# RAMBo.net
KiCad netlist of a schematic drawn in EAGLE
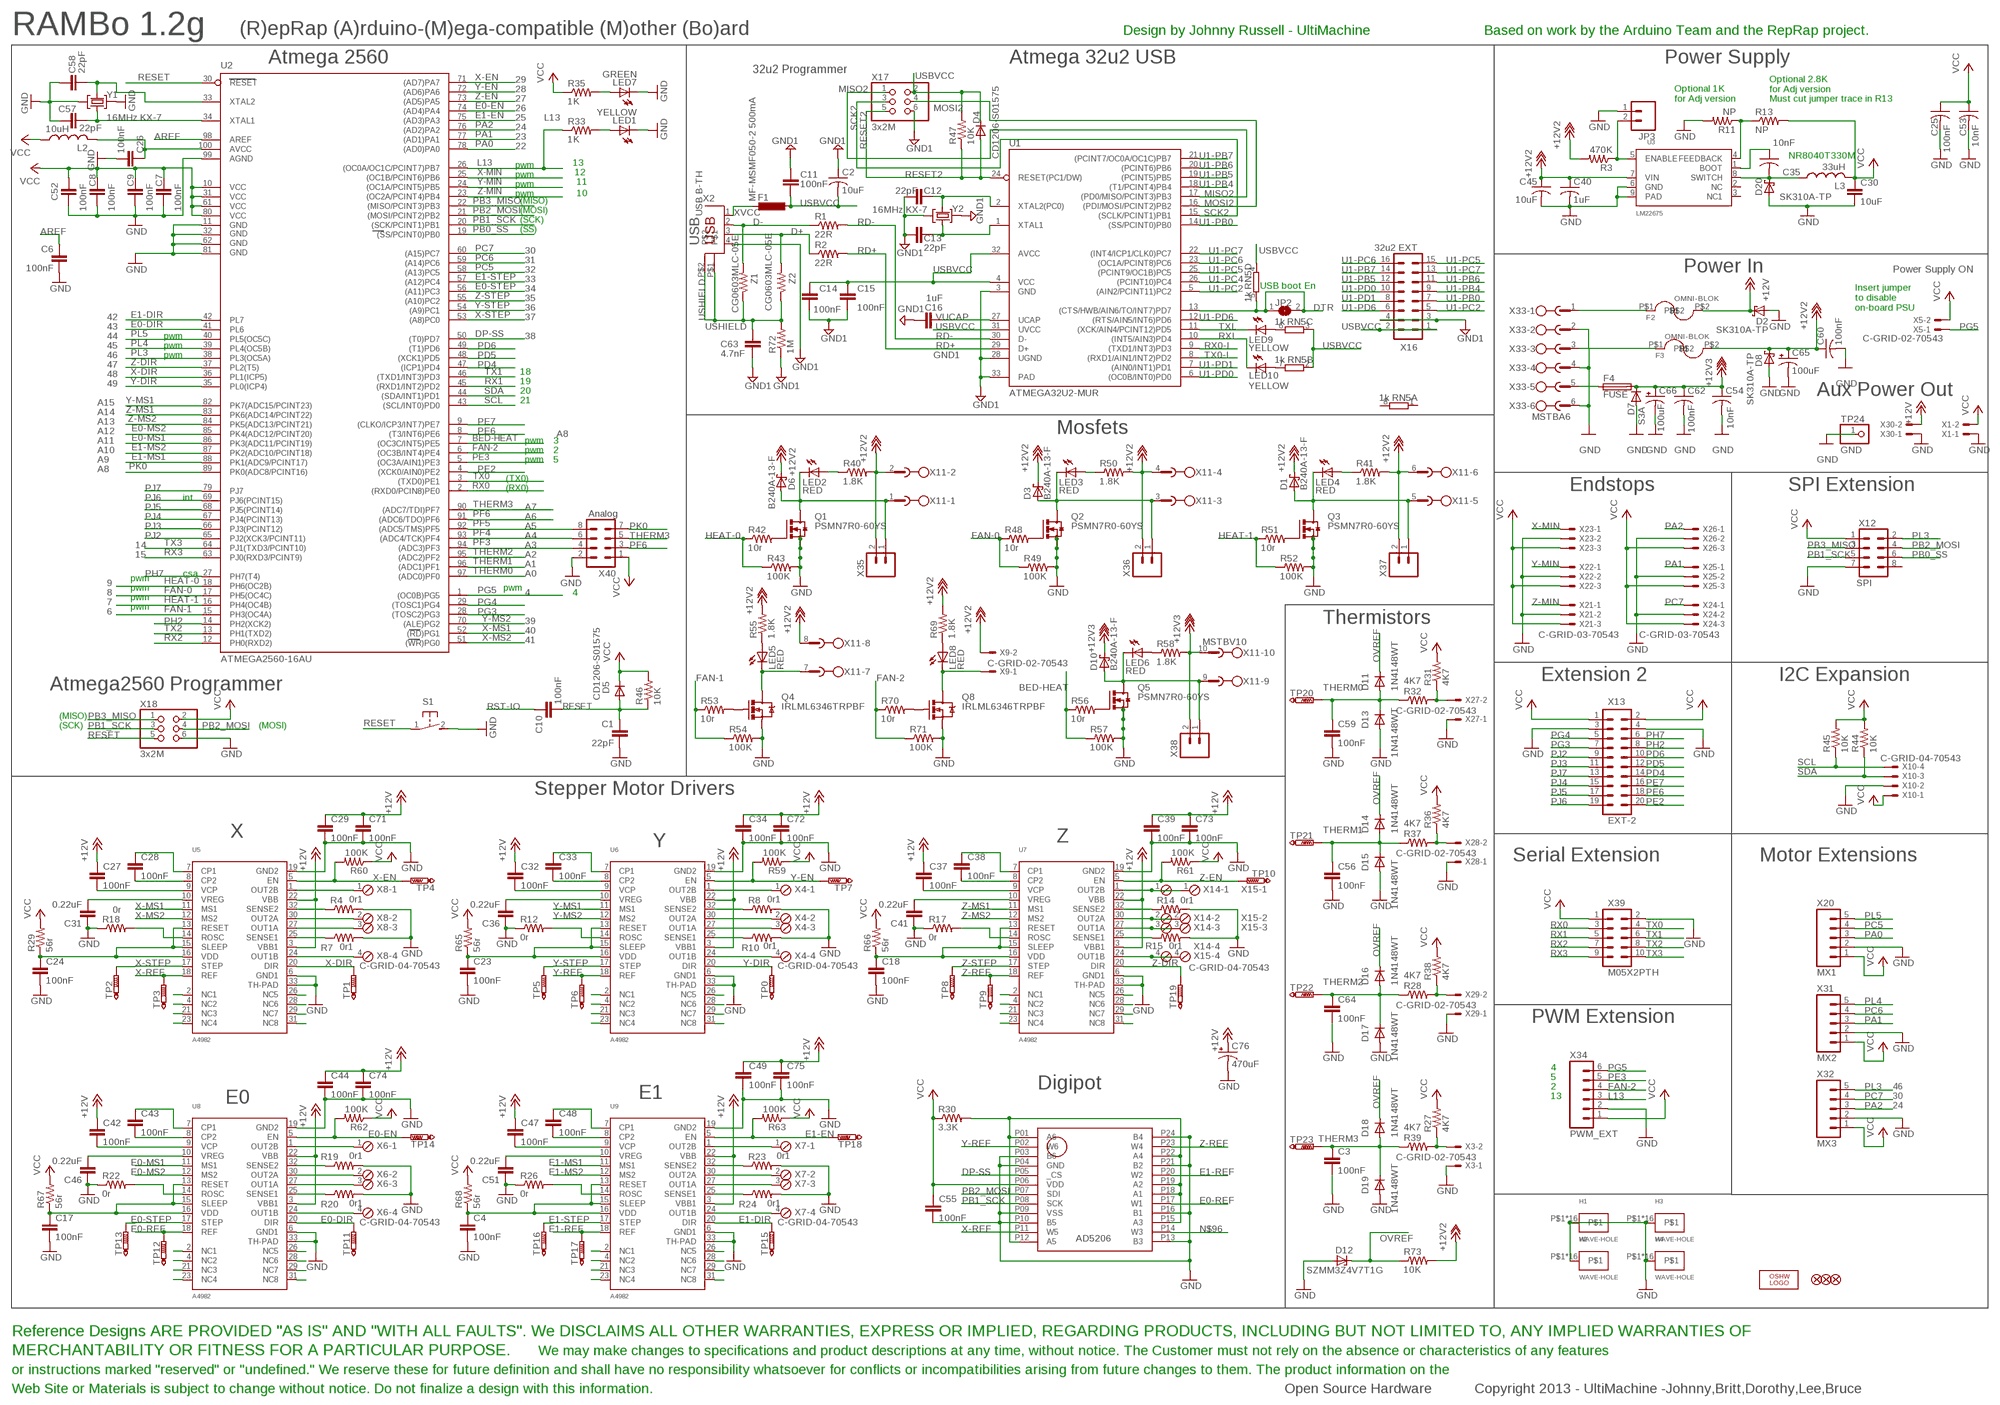
[diagram p0: schematic, sheet 1, part 1 of 2]
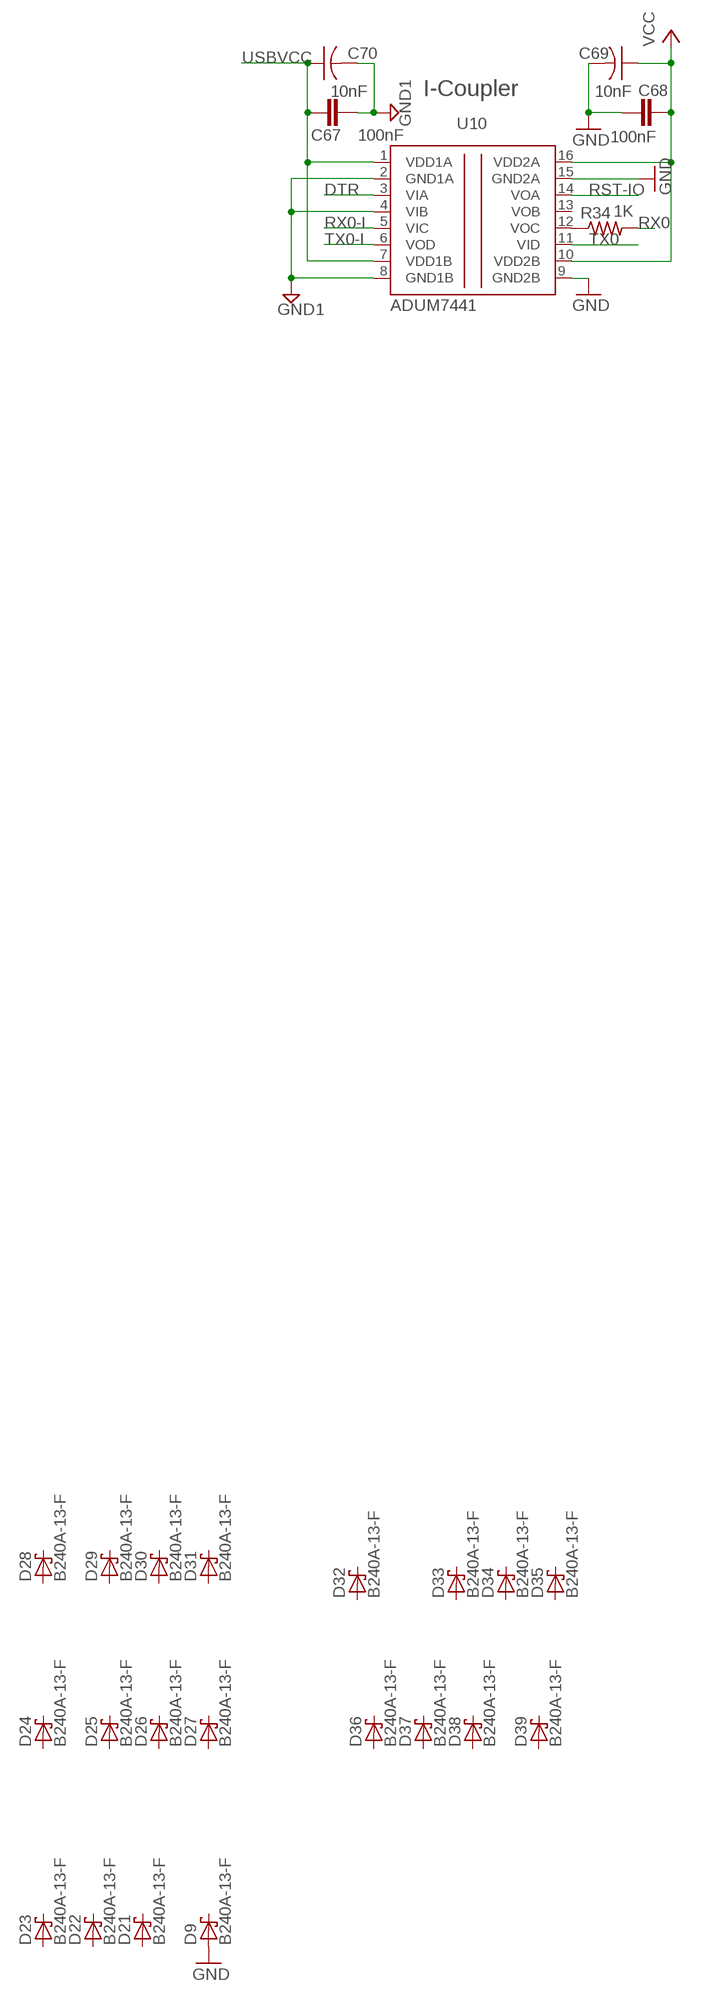
[diagram p1: schematic, sheet 1, part 2 of 2]

(export (version "E")
  (design (tool "Eeschema 10.0.6"))
  (components
    (comp (ref "C1")
      (value "22pF")
      (footprint "eagle-import:C0603")
      (libsource (lib "eagle-import") (part "resistor_C-EUC0603"))
    )
    (comp (ref "C2")
      (value "10uF")
      (footprint "eagle-import:C0805")
      (libsource (lib "eagle-import") (part "C-USC0805"))
    )
    (comp (ref "C3")
      (value "100nF")
      (footprint "eagle-import:C0603")
      (libsource (lib "eagle-import") (part "resistor_C-EUC0603"))
    )
    (comp (ref "C4")
      (value "100nF")
      (footprint "eagle-import:C0603")
      (libsource (lib "eagle-import") (part "resistor_C-EUC0603"))
    )
    (comp (ref "C6")
      (value "100nF")
      (footprint "eagle-import:C0603")
      (libsource (lib "eagle-import") (part "resistor_C-EUC0603"))
    )
    (comp (ref "C7")
      (value "100nF")
      (footprint "eagle-import:C0603")
      (libsource (lib "eagle-import") (part "resistor_C-EUC0603"))
    )
    (comp (ref "C8")
      (value "100nF")
      (footprint "eagle-import:C0603")
      (libsource (lib "eagle-import") (part "resistor_C-EUC0603"))
    )
    (comp (ref "C9")
      (value "100nF")
      (footprint "eagle-import:C0603")
      (libsource (lib "eagle-import") (part "resistor_C-EUC0603"))
    )
    (comp (ref "C10")
      (value "100nF")
      (footprint "eagle-import:C0603")
      (libsource (lib "eagle-import") (part "resistor_C-EUC0603"))
    )
    (comp (ref "C11")
      (value "100nF")
      (footprint "eagle-import:C0603")
      (libsource (lib "eagle-import") (part "resistor_C-EUC0603"))
    )
    (comp (ref "C12")
      (value "22pF")
      (footprint "eagle-import:C0603")
      (libsource (lib "eagle-import") (part "resistor_C-EUC0603"))
    )
    (comp (ref "C13")
      (value "22pF")
      (footprint "eagle-import:C0603")
      (libsource (lib "eagle-import") (part "resistor_C-EUC0603"))
    )
    (comp (ref "C14")
      (value "100nF")
      (footprint "eagle-import:C0603")
      (libsource (lib "eagle-import") (part "resistor_C-EUC0603"))
    )
    (comp (ref "C15")
      (value "100nF")
      (footprint "eagle-import:C0603")
      (libsource (lib "eagle-import") (part "resistor_C-EUC0603"))
    )
    (comp (ref "C16")
      (value "1uF")
      (footprint "eagle-import:C0603")
      (libsource (lib "eagle-import") (part "resistor_C-EUC0603"))
    )
    (comp (ref "C17")
      (value "100nF")
      (footprint "eagle-import:C0603")
      (libsource (lib "eagle-import") (part "resistor_C-EUC0603"))
    )
    (comp (ref "C18")
      (value "100nF")
      (footprint "eagle-import:C0603")
      (libsource (lib "eagle-import") (part "resistor_C-EUC0603"))
    )
    (comp (ref "C23")
      (value "100nF")
      (footprint "eagle-import:C0603")
      (libsource (lib "eagle-import") (part "resistor_C-EUC0603"))
    )
    (comp (ref "C24")
      (value "100nF")
      (footprint "eagle-import:C0603")
      (libsource (lib "eagle-import") (part "resistor_C-EUC0603"))
    )
    (comp (ref "C25")
      (value "100nF")
      (footprint "eagle-import:C0603")
      (libsource (lib "eagle-import") (part "C-USC0603"))
    )
    (comp (ref "C26")
      (value "100nF")
      (footprint "eagle-import:C0603")
      (libsource (lib "eagle-import") (part "resistor_C-EUC0603"))
    )
    (comp (ref "C27")
      (value "100nF")
      (footprint "eagle-import:C0603")
      (libsource (lib "eagle-import") (part "resistor_C-EUC0603"))
    )
    (comp (ref "C28")
      (value "100nF")
      (footprint "eagle-import:C0603")
      (libsource (lib "eagle-import") (part "resistor_C-EUC0603"))
    )
    (comp (ref "C29")
      (value "100nF")
      (footprint "eagle-import:C0603")
      (libsource (lib "eagle-import") (part "resistor_C-EUC0603"))
    )
    (comp (ref "C30")
      (value "10uF")
      (footprint "eagle-import:C1210K")
      (libsource (lib "eagle-import") (part "resistor_C-EUC1210K"))
    )
    (comp (ref "C31")
      (value "0.22uF")
      (footprint "eagle-import:C0603")
      (libsource (lib "eagle-import") (part "resistor_C-EUC0603"))
    )
    (comp (ref "C32")
      (value "100nF")
      (footprint "eagle-import:C0603")
      (libsource (lib "eagle-import") (part "resistor_C-EUC0603"))
    )
    (comp (ref "C33")
      (value "100nF")
      (footprint "eagle-import:C0603")
      (libsource (lib "eagle-import") (part "resistor_C-EUC0603"))
    )
    (comp (ref "C34")
      (value "100nF")
      (footprint "eagle-import:C0603")
      (libsource (lib "eagle-import") (part "resistor_C-EUC0603"))
    )
    (comp (ref "C35")
      (value "10nF")
      (footprint "eagle-import:C0603")
      (libsource (lib "eagle-import") (part "C-USC0603"))
    )
    (comp (ref "C36")
      (value "0.22uF")
      (footprint "eagle-import:C0603")
      (libsource (lib "eagle-import") (part "resistor_C-EUC0603"))
    )
    (comp (ref "C37")
      (value "100nF")
      (footprint "eagle-import:C0603")
      (libsource (lib "eagle-import") (part "resistor_C-EUC0603"))
    )
    (comp (ref "C38")
      (value "100nF")
      (footprint "eagle-import:C0603")
      (libsource (lib "eagle-import") (part "resistor_C-EUC0603"))
    )
    (comp (ref "C39")
      (value "100nF")
      (footprint "eagle-import:C0603")
      (libsource (lib "eagle-import") (part "resistor_C-EUC0603"))
    )
    (comp (ref "C40")
      (value "1uF")
      (footprint "eagle-import:C0805")
      (libsource (lib "eagle-import") (part "C-USC0805"))
    )
    (comp (ref "C41")
      (value "0.22uF")
      (footprint "eagle-import:C0603")
      (libsource (lib "eagle-import") (part "resistor_C-EUC0603"))
    )
    (comp (ref "C42")
      (value "100nF")
      (footprint "eagle-import:C0603")
      (libsource (lib "eagle-import") (part "resistor_C-EUC0603"))
    )
    (comp (ref "C43")
      (value "100nF")
      (footprint "eagle-import:C0603")
      (libsource (lib "eagle-import") (part "resistor_C-EUC0603"))
    )
    (comp (ref "C44")
      (value "100nF")
      (footprint "eagle-import:C0603")
      (libsource (lib "eagle-import") (part "resistor_C-EUC0603"))
    )
    (comp (ref "C45")
      (value "10uF")
      (footprint "eagle-import:C2220K")
      (libsource (lib "eagle-import") (part "C-USC2220K"))
    )
    (comp (ref "C46")
      (value "0.22uF")
      (footprint "eagle-import:C0603")
      (libsource (lib "eagle-import") (part "resistor_C-EUC0603"))
    )
    (comp (ref "C47")
      (value "100nF")
      (footprint "eagle-import:C0603")
      (libsource (lib "eagle-import") (part "resistor_C-EUC0603"))
    )
    (comp (ref "C48")
      (value "100nF")
      (footprint "eagle-import:C0603")
      (libsource (lib "eagle-import") (part "resistor_C-EUC0603"))
    )
    (comp (ref "C49")
      (value "100nF")
      (footprint "eagle-import:C0603")
      (libsource (lib "eagle-import") (part "resistor_C-EUC0603"))
    )
    (comp (ref "C51")
      (value "0.22uF")
      (footprint "eagle-import:C0603")
      (libsource (lib "eagle-import") (part "resistor_C-EUC0603"))
    )
    (comp (ref "C52")
      (value "100nF")
      (footprint "eagle-import:C0603")
      (libsource (lib "eagle-import") (part "resistor_C-EUC0603"))
    )
    (comp (ref "C53")
      (value "10nF")
      (footprint "eagle-import:C0603")
      (libsource (lib "eagle-import") (part "C-USC0603"))
    )
    (comp (ref "C54")
      (value "10nF")
      (footprint "eagle-import:C0603")
      (libsource (lib "eagle-import") (part "C-USC0603"))
    )
    (comp (ref "C55")
      (value "100nF")
      (footprint "eagle-import:C0603")
      (libsource (lib "eagle-import") (part "resistor_C-EUC0603"))
    )
    (comp (ref "C56")
      (value "100nF")
      (footprint "eagle-import:C0603")
      (libsource (lib "eagle-import") (part "resistor_C-EUC0603"))
    )
    (comp (ref "C57")
      (value "22pF")
      (footprint "eagle-import:C0603")
      (libsource (lib "eagle-import") (part "resistor_C-EUC0603"))
    )
    (comp (ref "C58")
      (value "22pF")
      (footprint "eagle-import:C0603")
      (libsource (lib "eagle-import") (part "resistor_C-EUC0603"))
    )
    (comp (ref "C59")
      (value "100nF")
      (footprint "eagle-import:C0603")
      (libsource (lib "eagle-import") (part "resistor_C-EUC0603"))
    )
    (comp (ref "C60")
      (value "100nF")
      (footprint "eagle-import:C0603")
      (libsource (lib "eagle-import") (part "C-USC0603"))
    )
    (comp (ref "C62")
      (value "100nF")
      (footprint "eagle-import:C0603")
      (libsource (lib "eagle-import") (part "C-USC0603"))
    )
    (comp (ref "C63")
      (value "4.7nF")
      (footprint "eagle-import:C0402")
      (libsource (lib "eagle-import") (part "C-EUC0402"))
    )
    (comp (ref "C64")
      (value "100nF")
      (footprint "eagle-import:C0603")
      (libsource (lib "eagle-import") (part "resistor_C-EUC0603"))
    )
    (comp (ref "C65")
      (value "100uF")
      (footprint "eagle-import:E3,5-8")
      (libsource (lib "eagle-import") (part "CPOL-USE3.5-8"))
    )
    (comp (ref "C66")
      (value "100uF")
      (footprint "eagle-import:E3,5-8")
      (libsource (lib "eagle-import") (part "CPOL-USE3.5-8"))
    )
    (comp (ref "C67")
      (value "100nF")
      (footprint "eagle-import:C0603")
      (libsource (lib "eagle-import") (part "resistor_C-EUC0603"))
    )
    (comp (ref "C68")
      (value "100nF")
      (footprint "eagle-import:C0603")
      (libsource (lib "eagle-import") (part "resistor_C-EUC0603"))
    )
    (comp (ref "C69")
      (value "10nF")
      (footprint "eagle-import:C0603")
      (libsource (lib "eagle-import") (part "C-USC0603"))
    )
    (comp (ref "C70")
      (value "10nF")
      (footprint "eagle-import:C0603")
      (libsource (lib "eagle-import") (part "C-USC0603"))
    )
    (comp (ref "C71")
      (value "100nF")
      (footprint "eagle-import:C0603")
      (libsource (lib "eagle-import") (part "resistor_C-EUC0603"))
    )
    (comp (ref "C72")
      (value "100nF")
      (footprint "eagle-import:C0603")
      (libsource (lib "eagle-import") (part "resistor_C-EUC0603"))
    )
    (comp (ref "C73")
      (value "100nF")
      (footprint "eagle-import:C0603")
      (libsource (lib "eagle-import") (part "resistor_C-EUC0603"))
    )
    (comp (ref "C74")
      (value "100nF")
      (footprint "eagle-import:C0603")
      (libsource (lib "eagle-import") (part "resistor_C-EUC0603"))
    )
    (comp (ref "C75")
      (value "100nF")
      (footprint "eagle-import:C0603")
      (libsource (lib "eagle-import") (part "resistor_C-EUC0603"))
    )
    (comp (ref "C76")
      (value "470uF")
      (footprint "eagle-import:C12,5-5")
      (libsource (lib "eagle-import") (part "CPOL-USC12,5-5"))
    )
    (comp (ref "D1")
      (value "B240A-13-F")
      (footprint "eagle-import:SMA-SM")
      (libsource (lib "eagle-import") (part "SCHOTTKY-DIODE"))
    )
    (comp (ref "D2")
      (value "SK310A-TP")
      (footprint "eagle-import:SMA-SM")
      (libsource (lib "eagle-import") (part "SCHOTTKY-DIODE"))
    )
    (comp (ref "D3")
      (value "B240A-13-F")
      (footprint "eagle-import:SMA-SM")
      (libsource (lib "eagle-import") (part "SCHOTTKY-DIODE"))
    )
    (comp (ref "D4")
      (value "CD1206-S01575")
      (footprint "eagle-import:MINIMELF")
      (libsource (lib "eagle-import") (part "DIODE-MINIMELF"))
    )
    (comp (ref "D5")
      (value "CD1206-S01575")
      (footprint "eagle-import:MINIMELF")
      (libsource (lib "eagle-import") (part "DIODE-MINIMELF"))
    )
    (comp (ref "D6")
      (value "B240A-13-F")
      (footprint "eagle-import:SMA-SM")
      (libsource (lib "eagle-import") (part "SCHOTTKY-DIODE"))
    )
    (comp (ref "D7")
      (value "S3A")
      (footprint "eagle-import:DO-214AB")
      (libsource (lib "eagle-import") (part "DIODE-D0-214AB"))
    )
    (comp (ref "D8")
      (value "SK310A-TP")
      (footprint "eagle-import:SMA-SM")
      (libsource (lib "eagle-import") (part "SCHOTTKY-DIODE"))
    )
    (comp (ref "D9")
      (value "B240A-13-F")
      (footprint "eagle-import:SMA-SM")
      (libsource (lib "eagle-import") (part "SCHOTTKY-DIODE"))
    )
    (comp (ref "D10")
      (value "B240A-13-F")
      (footprint "eagle-import:SMA-SM")
      (libsource (lib "eagle-import") (part "SCHOTTKY-DIODE"))
    )
    (comp (ref "D11")
      (value "1N4148WT")
      (footprint "eagle-import:SOD523")
      (libsource (lib "eagle-import") (part "1N4148WT"))
    )
    (comp (ref "D12")
      (value "SZMM3Z4V7T1G")
      (footprint "eagle-import:SOD323-R")
      (libsource (lib "eagle-import") (part "ZENER-DIODESOD323"))
    )
    (comp (ref "D13")
      (value "1N4148WT")
      (footprint "eagle-import:SOD523")
      (libsource (lib "eagle-import") (part "1N4148WT"))
    )
    (comp (ref "D14")
      (value "1N4148WT")
      (footprint "eagle-import:SOD523")
      (libsource (lib "eagle-import") (part "1N4148WT"))
    )
    (comp (ref "D15")
      (value "1N4148WT")
      (footprint "eagle-import:SOD523")
      (libsource (lib "eagle-import") (part "1N4148WT"))
    )
    (comp (ref "D16")
      (value "1N4148WT")
      (footprint "eagle-import:SOD523")
      (libsource (lib "eagle-import") (part "1N4148WT"))
    )
    (comp (ref "D17")
      (value "1N4148WT")
      (footprint "eagle-import:SOD523")
      (libsource (lib "eagle-import") (part "1N4148WT"))
    )
    (comp (ref "D18")
      (value "1N4148WT")
      (footprint "eagle-import:SOD523")
      (libsource (lib "eagle-import") (part "1N4148WT"))
    )
    (comp (ref "D19")
      (value "1N4148WT")
      (footprint "eagle-import:SOD523")
      (libsource (lib "eagle-import") (part "1N4148WT"))
    )
    (comp (ref "D20")
      (value "SK310A-TP")
      (footprint "eagle-import:SMA-SM")
      (libsource (lib "eagle-import") (part "SCHOTTKY-DIODE"))
    )
    (comp (ref "D21")
      (value "B240A-13-F")
      (footprint "eagle-import:SMA-SM")
      (libsource (lib "eagle-import") (part "SCHOTTKY-DIODE"))
    )
    (comp (ref "D22")
      (value "B240A-13-F")
      (footprint "eagle-import:SMA-SM")
      (libsource (lib "eagle-import") (part "SCHOTTKY-DIODE"))
    )
    (comp (ref "D23")
      (value "B240A-13-F")
      (footprint "eagle-import:SMA-SM")
      (libsource (lib "eagle-import") (part "SCHOTTKY-DIODE"))
    )
    (comp (ref "D24")
      (value "B240A-13-F")
      (footprint "eagle-import:SMA-SM")
      (libsource (lib "eagle-import") (part "SCHOTTKY-DIODE"))
    )
    (comp (ref "D25")
      (value "B240A-13-F")
      (footprint "eagle-import:SMA-SM")
      (libsource (lib "eagle-import") (part "SCHOTTKY-DIODE"))
    )
    (comp (ref "D26")
      (value "B240A-13-F")
      (footprint "eagle-import:SMA-SM")
      (libsource (lib "eagle-import") (part "SCHOTTKY-DIODE"))
    )
    (comp (ref "D27")
      (value "B240A-13-F")
      (footprint "eagle-import:SMA-SM")
      (libsource (lib "eagle-import") (part "SCHOTTKY-DIODE"))
    )
    (comp (ref "D28")
      (value "B240A-13-F")
      (footprint "eagle-import:SMA-SM")
      (libsource (lib "eagle-import") (part "SCHOTTKY-DIODE"))
    )
    (comp (ref "D29")
      (value "B240A-13-F")
      (footprint "eagle-import:SMA-SM")
      (libsource (lib "eagle-import") (part "SCHOTTKY-DIODE"))
    )
    (comp (ref "D30")
      (value "B240A-13-F")
      (footprint "eagle-import:SMA-SM")
      (libsource (lib "eagle-import") (part "SCHOTTKY-DIODE"))
    )
    (comp (ref "D31")
      (value "B240A-13-F")
      (footprint "eagle-import:SMA-SM")
      (libsource (lib "eagle-import") (part "SCHOTTKY-DIODE"))
    )
    (comp (ref "D32")
      (value "B240A-13-F")
      (footprint "eagle-import:SMA-SM")
      (libsource (lib "eagle-import") (part "SCHOTTKY-DIODE"))
    )
    (comp (ref "D33")
      (value "B240A-13-F")
      (footprint "eagle-import:SMA-SM")
      (libsource (lib "eagle-import") (part "SCHOTTKY-DIODE"))
    )
    (comp (ref "D34")
      (value "B240A-13-F")
      (footprint "eagle-import:SMA-SM")
      (libsource (lib "eagle-import") (part "SCHOTTKY-DIODE"))
    )
    (comp (ref "D35")
      (value "B240A-13-F")
      (footprint "eagle-import:SMA-SM")
      (libsource (lib "eagle-import") (part "SCHOTTKY-DIODE"))
    )
    (comp (ref "D36")
      (value "B240A-13-F")
      (footprint "eagle-import:SMA-SM")
      (libsource (lib "eagle-import") (part "SCHOTTKY-DIODE"))
    )
    (comp (ref "D37")
      (value "B240A-13-F")
      (footprint "eagle-import:SMA-SM")
      (libsource (lib "eagle-import") (part "SCHOTTKY-DIODE"))
    )
    (comp (ref "D38")
      (value "B240A-13-F")
      (footprint "eagle-import:SMA-SM")
      (libsource (lib "eagle-import") (part "SCHOTTKY-DIODE"))
    )
    (comp (ref "D39")
      (value "B240A-13-F")
      (footprint "eagle-import:SMA-SM")
      (libsource (lib "eagle-import") (part "SCHOTTKY-DIODE"))
    )
    (comp (ref "F1")
      (value "MF-MSMF050-2 500mA")
      (footprint "eagle-import:L1812")
      (libsource (lib "eagle-import") (part "L-EUL1812"))
    )
    (comp (ref "F2")
      (value "OMNI-BLOK")
      (footprint "eagle-import:OMNI-BLOK")
      (libsource (lib "eagle-import") (part "OMNI-BLOK"))
    )
    (comp (ref "F3")
      (value "OMNI-BLOK")
      (footprint "eagle-import:OMNI-BLOK")
      (libsource (lib "eagle-import") (part "OMNI-BLOK"))
    )
    (comp (ref "F4")
      (value "FUSE")
      (footprint "eagle-import:FUSE-ATO-SMD")
      (libsource (lib "eagle-import") (part "FUSE"))
    )
    (comp (ref "FID1")
      (value "FIDUCIAL1X2")
      (footprint "eagle-import:FIDUCIAL-1X2")
      (libsource (lib "eagle-import") (part "FIDUCIAL1X2"))
    )
    (comp (ref "FID2")
      (value "FIDUCIAL1X2")
      (footprint "eagle-import:FIDUCIAL-1X2")
      (libsource (lib "eagle-import") (part "FIDUCIAL1X2"))
    )
    (comp (ref "FID3")
      (value "FIDUCIAL1X2")
      (footprint "eagle-import:FIDUCIAL-1X2")
      (libsource (lib "eagle-import") (part "FIDUCIAL1X2"))
    )
    (comp (ref "H1")
      (value "WAVE-HOLE")
      (footprint "eagle-import:3,0-WAVE-HOLE")
      (libsource (lib "eagle-import") (part "WAVE-HOLE"))
    )
    (comp (ref "H2")
      (value "WAVE-HOLE")
      (footprint "eagle-import:3,0-WAVE-HOLE")
      (libsource (lib "eagle-import") (part "WAVE-HOLE"))
    )
    (comp (ref "H3")
      (value "WAVE-HOLE")
      (footprint "eagle-import:3,0-WAVE-HOLE")
      (libsource (lib "eagle-import") (part "WAVE-HOLE"))
    )
    (comp (ref "H4")
      (value "WAVE-HOLE")
      (footprint "eagle-import:3,0-WAVE-HOLE")
      (libsource (lib "eagle-import") (part "WAVE-HOLE"))
    )
    (comp (ref "JP2") (value "SJ") (footprint "eagle-import:SJ") (libsource (lib "eagle-import") (part "SJ")))
    (comp (ref "JP3")
      (value "M02PTH")
      (footprint "eagle-import:1X02")
      (libsource (lib "eagle-import") (part "M02PTH"))
    )
    (comp (ref "L2")
      (value "10uH")
      (footprint "eagle-import:C0805")
      (libsource (lib "eagle-import") (part "L-US"))
    )
    (comp (ref "L3")
      (value "33uH")
      (footprint "eagle-import:NR8040")
      (libsource (lib "eagle-import") (part "L-USNR8040"))
    )
    (comp (ref "LED1")
      (value "YELLOW")
      (footprint "eagle-import:CHIP-LED0805")
      (libsource (lib "eagle-import") (part "LEDCHIP-LED0805"))
    )
    (comp (ref "LED2")
      (value "RED")
      (footprint "eagle-import:CHIP-LED0805")
      (libsource (lib "eagle-import") (part "LEDCHIP-LED0805"))
    )
    (comp (ref "LED3")
      (value "RED")
      (footprint "eagle-import:CHIP-LED0805")
      (libsource (lib "eagle-import") (part "LEDCHIP-LED0805"))
    )
    (comp (ref "LED4")
      (value "RED")
      (footprint "eagle-import:CHIP-LED0805")
      (libsource (lib "eagle-import") (part "LEDCHIP-LED0805"))
    )
    (comp (ref "LED5")
      (value "RED")
      (footprint "eagle-import:CHIP-LED0805")
      (libsource (lib "eagle-import") (part "LEDCHIP-LED0805"))
    )
    (comp (ref "LED6")
      (value "RED")
      (footprint "eagle-import:CHIP-LED0805")
      (libsource (lib "eagle-import") (part "LEDCHIP-LED0805"))
    )
    (comp (ref "LED7")
      (value "GREEN")
      (footprint "eagle-import:CHIP-LED0805")
      (libsource (lib "eagle-import") (part "LEDCHIP-LED0805"))
    )
    (comp (ref "LED8")
      (value "RED")
      (footprint "eagle-import:CHIP-LED0805")
      (libsource (lib "eagle-import") (part "LEDCHIP-LED0805"))
    )
    (comp (ref "LED9")
      (value "YELLOW")
      (footprint "eagle-import:CHIP-LED0805")
      (libsource (lib "eagle-import") (part "LEDCHIP-LED0805"))
    )
    (comp (ref "LED10")
      (value "YELLOW")
      (footprint "eagle-import:CHIP-LED0805")
      (libsource (lib "eagle-import") (part "LEDCHIP-LED0805"))
    )
    (comp (ref "LOGO1")
      (value "OSHW_LOGO_8MILX0150-NT")
      (footprint "eagle-import:OSHW_8X150_NOTEXT")
      (libsource (lib "eagle-import") (part "OSHW_LOGO_8MILX0150-NT"))
    )
    (comp (ref "Q1")
      (value "PSMN7R0-60YS")
      (footprint "eagle-import:SOT669")
      (libsource (lib "eagle-import") (part "PH7030L"))
    )
    (comp (ref "Q2")
      (value "PSMN7R0-60YS")
      (footprint "eagle-import:SOT669")
      (libsource (lib "eagle-import") (part "PH7030L"))
    )
    (comp (ref "Q3")
      (value "PSMN7R0-60YS")
      (footprint "eagle-import:SOT669")
      (libsource (lib "eagle-import") (part "PH7030L"))
    )
    (comp (ref "Q4")
      (value "IRLML6346TRPBF")
      (footprint "eagle-import:SOT23-3")
      (libsource (lib "eagle-import") (part "MOSFET-NCHANNELSMD"))
    )
    (comp (ref "Q5")
      (value "PSMN7R0-60YS")
      (footprint "eagle-import:SOT669")
      (libsource (lib "eagle-import") (part "PH7030L"))
    )
    (comp (ref "Q8")
      (value "IRLML6346TRPBF")
      (footprint "eagle-import:SOT23-3")
      (libsource (lib "eagle-import") (part "MOSFET-NCHANNELSMD"))
    )
    (comp (ref "R1")
      (value "22R")
      (footprint "eagle-import:R0402")
      (libsource (lib "eagle-import") (part "R-US_R0402"))
    )
    (comp (ref "R2")
      (value "22R")
      (footprint "eagle-import:R0402")
      (libsource (lib "eagle-import") (part "R-US_R0402"))
    )
    (comp (ref "R3")
      (value "470K")
      (footprint "eagle-import:R0603")
      (libsource (lib "eagle-import") (part "resistor_R-US_R0603"))
    )
    (comp (ref "R4")
      (value "0r1")
      (footprint "eagle-import:R1206")
      (libsource (lib "eagle-import") (part "resistor_R-US_R1206"))
    )
    (comp (ref "R7")
      (value "0r1")
      (footprint "eagle-import:R1206")
      (libsource (lib "eagle-import") (part "resistor_R-US_R1206"))
    )
    (comp (ref "R8")
      (value "0r1")
      (footprint "eagle-import:R1206")
      (libsource (lib "eagle-import") (part "resistor_R-US_R1206"))
    )
    (comp (ref "R10")
      (value "0r1")
      (footprint "eagle-import:R1206")
      (libsource (lib "eagle-import") (part "resistor_R-US_R1206"))
    )
    (comp (ref "R11")
      (value "NP")
      (footprint "eagle-import:R0603")
      (libsource (lib "eagle-import") (part "resistor_R-US_R0603"))
    )
    (comp (ref "R12")
      (value "0r")
      (footprint "eagle-import:R0603")
      (libsource (lib "eagle-import") (part "resistor_R-US_R0603"))
    )
    (comp (ref "R13")
      (value "NP")
      (footprint "eagle-import:R0603")
      (libsource (lib "eagle-import") (part "resistor_R-US_R0603"))
    )
    (comp (ref "R14")
      (value "0r1")
      (footprint "eagle-import:R1206")
      (libsource (lib "eagle-import") (part "resistor_R-US_R1206"))
    )
    (comp (ref "R15")
      (value "0r1")
      (footprint "eagle-import:R1206")
      (libsource (lib "eagle-import") (part "resistor_R-US_R1206"))
    )
    (comp (ref "R17")
      (value "0r")
      (footprint "eagle-import:R0603")
      (libsource (lib "eagle-import") (part "resistor_R-US_R0603"))
    )
    (comp (ref "R18")
      (value "0r")
      (footprint "eagle-import:R0603")
      (libsource (lib "eagle-import") (part "resistor_R-US_R0603"))
    )
    (comp (ref "R19")
      (value "0r1")
      (footprint "eagle-import:R1206")
      (libsource (lib "eagle-import") (part "resistor_R-US_R1206"))
    )
    (comp (ref "R20")
      (value "0r1")
      (footprint "eagle-import:R1206")
      (libsource (lib "eagle-import") (part "resistor_R-US_R1206"))
    )
    (comp (ref "R22")
      (value "0r")
      (footprint "eagle-import:R0603")
      (libsource (lib "eagle-import") (part "resistor_R-US_R0603"))
    )
    (comp (ref "R23")
      (value "0r1")
      (footprint "eagle-import:R1206")
      (libsource (lib "eagle-import") (part "resistor_R-US_R1206"))
    )
    (comp (ref "R24")
      (value "0r1")
      (footprint "eagle-import:R1206")
      (libsource (lib "eagle-import") (part "resistor_R-US_R1206"))
    )
    (comp (ref "R26")
      (value "0r")
      (footprint "eagle-import:R0603")
      (libsource (lib "eagle-import") (part "resistor_R-US_R0603"))
    )
    (comp (ref "R27")
      (value "4K7")
      (footprint "eagle-import:R0603")
      (libsource (lib "eagle-import") (part "resistor_R-US_R0603"))
    )
    (comp (ref "R28")
      (value "4K7")
      (footprint "eagle-import:R0603")
      (libsource (lib "eagle-import") (part "resistor_R-US_R0603"))
    )
    (comp (ref "R29")
      (value "56r")
      (footprint "eagle-import:R0603")
      (libsource (lib "eagle-import") (part "resistor_R-US_R0603"))
    )
    (comp (ref "R30")
      (value "3.3K")
      (footprint "eagle-import:R0603")
      (libsource (lib "eagle-import") (part "resistor_R-US_R0603"))
    )
    (comp (ref "R31")
      (value "4K7")
      (footprint "eagle-import:R0603")
      (libsource (lib "eagle-import") (part "resistor_R-US_R0603"))
    )
    (comp (ref "R32")
      (value "4K7")
      (footprint "eagle-import:R0603")
      (libsource (lib "eagle-import") (part "resistor_R-US_R0603"))
    )
    (comp (ref "R33")
      (value "1K")
      (footprint "eagle-import:R0603")
      (libsource (lib "eagle-import") (part "resistor_R-US_R0603"))
    )
    (comp (ref "R34")
      (value "1K")
      (footprint "eagle-import:R0603")
      (libsource (lib "eagle-import") (part "resistor_R-US_R0603"))
    )
    (comp (ref "R35")
      (value "1K")
      (footprint "eagle-import:R0603")
      (libsource (lib "eagle-import") (part "resistor_R-US_R0603"))
    )
    (comp (ref "R36")
      (value "4K7")
      (footprint "eagle-import:R0603")
      (libsource (lib "eagle-import") (part "resistor_R-US_R0603"))
    )
    (comp (ref "R37")
      (value "4K7")
      (footprint "eagle-import:R0603")
      (libsource (lib "eagle-import") (part "resistor_R-US_R0603"))
    )
    (comp (ref "R38")
      (value "4K7")
      (footprint "eagle-import:R0603")
      (libsource (lib "eagle-import") (part "resistor_R-US_R0603"))
    )
    (comp (ref "R39")
      (value "4K7")
      (footprint "eagle-import:R0603")
      (libsource (lib "eagle-import") (part "resistor_R-US_R0603"))
    )
    (comp (ref "R40")
      (value "1.8K")
      (footprint "eagle-import:R0603")
      (libsource (lib "eagle-import") (part "resistor_R-US_R0603"))
    )
    (comp (ref "R41")
      (value "1.8K")
      (footprint "eagle-import:R0603")
      (libsource (lib "eagle-import") (part "resistor_R-US_R0603"))
    )
    (comp (ref "R42")
      (value "10r")
      (footprint "eagle-import:R0603")
      (libsource (lib "eagle-import") (part "resistor_R-US_R0603"))
    )
    (comp (ref "R43")
      (value "100K")
      (footprint "eagle-import:R0603")
      (libsource (lib "eagle-import") (part "resistor_R-US_R0603"))
    )
    (comp (ref "R44")
      (value "10K")
      (footprint "eagle-import:R0603")
      (libsource (lib "eagle-import") (part "resistor_R-US_R0603"))
    )
    (comp (ref "R45")
      (value "10K")
      (footprint "eagle-import:R0603")
      (libsource (lib "eagle-import") (part "resistor_R-US_R0603"))
    )
    (comp (ref "R46")
      (value "10K")
      (footprint "eagle-import:R0603")
      (libsource (lib "eagle-import") (part "resistor_R-US_R0603"))
    )
    (comp (ref "R47")
      (value "10K")
      (footprint "eagle-import:R0603")
      (libsource (lib "eagle-import") (part "resistor_R-US_R0603"))
    )
    (comp (ref "R48")
      (value "10r")
      (footprint "eagle-import:R0603")
      (libsource (lib "eagle-import") (part "resistor_R-US_R0603"))
    )
    (comp (ref "R49")
      (value "100K")
      (footprint "eagle-import:R0603")
      (libsource (lib "eagle-import") (part "resistor_R-US_R0603"))
    )
    (comp (ref "R50")
      (value "1.8K")
      (footprint "eagle-import:R0603")
      (libsource (lib "eagle-import") (part "resistor_R-US_R0603"))
    )
    (comp (ref "R51")
      (value "10r")
      (footprint "eagle-import:R0603")
      (libsource (lib "eagle-import") (part "resistor_R-US_R0603"))
    )
    (comp (ref "R52")
      (value "100K")
      (footprint "eagle-import:R0603")
      (libsource (lib "eagle-import") (part "resistor_R-US_R0603"))
    )
    (comp (ref "R53")
      (value "10r")
      (footprint "eagle-import:R0603")
      (libsource (lib "eagle-import") (part "resistor_R-US_R0603"))
    )
    (comp (ref "R54")
      (value "100K")
      (footprint "eagle-import:R0603")
      (libsource (lib "eagle-import") (part "resistor_R-US_R0603"))
    )
    (comp (ref "R55")
      (value "1.8K")
      (footprint "eagle-import:R0603")
      (libsource (lib "eagle-import") (part "resistor_R-US_R0603"))
    )
    (comp (ref "R56")
      (value "10r")
      (footprint "eagle-import:R0603")
      (libsource (lib "eagle-import") (part "resistor_R-US_R0603"))
    )
    (comp (ref "R57")
      (value "100K")
      (footprint "eagle-import:R0603")
      (libsource (lib "eagle-import") (part "resistor_R-US_R0603"))
    )
    (comp (ref "R58")
      (value "1.8K")
      (footprint "eagle-import:R0603")
      (libsource (lib "eagle-import") (part "resistor_R-US_R0603"))
    )
    (comp (ref "R59")
      (value "100K")
      (footprint "eagle-import:R0603")
      (libsource (lib "eagle-import") (part "resistor_R-US_R0603"))
    )
    (comp (ref "R60")
      (value "100K")
      (footprint "eagle-import:R0603")
      (libsource (lib "eagle-import") (part "resistor_R-US_R0603"))
    )
    (comp (ref "R61")
      (value "100K")
      (footprint "eagle-import:R0603")
      (libsource (lib "eagle-import") (part "resistor_R-US_R0603"))
    )
    (comp (ref "R62")
      (value "100K")
      (footprint "eagle-import:R0603")
      (libsource (lib "eagle-import") (part "resistor_R-US_R0603"))
    )
    (comp (ref "R63")
      (value "100K")
      (footprint "eagle-import:R0603")
      (libsource (lib "eagle-import") (part "resistor_R-US_R0603"))
    )
    (comp (ref "R65")
      (value "56r")
      (footprint "eagle-import:R0603")
      (libsource (lib "eagle-import") (part "resistor_R-US_R0603"))
    )
    (comp (ref "R66")
      (value "56r")
      (footprint "eagle-import:R0603")
      (libsource (lib "eagle-import") (part "resistor_R-US_R0603"))
    )
    (comp (ref "R67")
      (value "56r")
      (footprint "eagle-import:R0603")
      (libsource (lib "eagle-import") (part "resistor_R-US_R0603"))
    )
    (comp (ref "R68")
      (value "56r")
      (footprint "eagle-import:R0603")
      (libsource (lib "eagle-import") (part "resistor_R-US_R0603"))
    )
    (comp (ref "R69")
      (value "1.8K")
      (footprint "eagle-import:R0603")
      (libsource (lib "eagle-import") (part "resistor_R-US_R0603"))
    )
    (comp (ref "R70")
      (value "10r")
      (footprint "eagle-import:R0603")
      (libsource (lib "eagle-import") (part "resistor_R-US_R0603"))
    )
    (comp (ref "R71")
      (value "100K")
      (footprint "eagle-import:R0603")
      (libsource (lib "eagle-import") (part "resistor_R-US_R0603"))
    )
    (comp (ref "R72")
      (value "1M")
      (footprint "eagle-import:R0402")
      (libsource (lib "eagle-import") (part "R-US_R0402"))
    )
    (comp (ref "R73")
      (value "10K")
      (footprint "eagle-import:R0603")
      (libsource (lib "eagle-import") (part "resistor_R-US_R0603"))
    )
    (comp (ref "RN5")
      (value "1k")
      (footprint "eagle-import:CAY16")
      (libsource (lib "eagle-import") (part "4R-NCAY16"))
    )
    (comp (ref "S1")
      (value "31-XX")
      (footprint "eagle-import:B3F-31XX")
      (libsource (lib "eagle-import") (part "31-XX"))
    )
    (comp (ref "TP0")
      (value "PTR1B1,27TH")
      (footprint "eagle-import:B1,27TH")
      (libsource (lib "eagle-import") (part "PTR1B1,27TH"))
    )
    (comp (ref "TP1")
      (value "PTR1B1,27TH")
      (footprint "eagle-import:B1,27TH")
      (libsource (lib "eagle-import") (part "PTR1B1,27TH"))
    )
    (comp (ref "TP2")
      (value "PTR1B1,27TH")
      (footprint "eagle-import:B1,27TH")
      (libsource (lib "eagle-import") (part "PTR1B1,27TH"))
    )
    (comp (ref "TP3")
      (value "PTR1B1,27TH")
      (footprint "eagle-import:B1,27TH")
      (libsource (lib "eagle-import") (part "PTR1B1,27TH"))
    )
    (comp (ref "TP4")
      (value "PTR1B1,27TH")
      (footprint "eagle-import:B1,27TH")
      (libsource (lib "eagle-import") (part "PTR1B1,27TH"))
    )
    (comp (ref "TP5")
      (value "PTR1B1,27TH")
      (footprint "eagle-import:B1,27TH")
      (libsource (lib "eagle-import") (part "PTR1B1,27TH"))
    )
    (comp (ref "TP6")
      (value "PTR1B1,27TH")
      (footprint "eagle-import:B1,27TH")
      (libsource (lib "eagle-import") (part "PTR1B1,27TH"))
    )
    (comp (ref "TP7")
      (value "PTR1B1,27TH")
      (footprint "eagle-import:B1,27TH")
      (libsource (lib "eagle-import") (part "PTR1B1,27TH"))
    )
    (comp (ref "TP8")
      (value "PTR1B1,27TH")
      (footprint "eagle-import:B1,27TH")
      (libsource (lib "eagle-import") (part "PTR1B1,27TH"))
    )
    (comp (ref "TP9")
      (value "PTR1B1,27TH")
      (footprint "eagle-import:B1,27TH")
      (libsource (lib "eagle-import") (part "PTR1B1,27TH"))
    )
    (comp (ref "TP10")
      (value "PTR1B1,27TH")
      (footprint "eagle-import:B1,27TH")
      (libsource (lib "eagle-import") (part "PTR1B1,27TH"))
    )
    (comp (ref "TP11")
      (value "PTR1B1,27TH")
      (footprint "eagle-import:B1,27TH")
      (libsource (lib "eagle-import") (part "PTR1B1,27TH"))
    )
    (comp (ref "TP12")
      (value "PTR1B1,27TH")
      (footprint "eagle-import:B1,27TH")
      (libsource (lib "eagle-import") (part "PTR1B1,27TH"))
    )
    (comp (ref "TP13")
      (value "PTR1B1,27TH")
      (footprint "eagle-import:B1,27TH")
      (libsource (lib "eagle-import") (part "PTR1B1,27TH"))
    )
    (comp (ref "TP14")
      (value "PTR1B1,27TH")
      (footprint "eagle-import:B1,27TH")
      (libsource (lib "eagle-import") (part "PTR1B1,27TH"))
    )
    (comp (ref "TP15")
      (value "PTR1B1,27TH")
      (footprint "eagle-import:B1,27TH")
      (libsource (lib "eagle-import") (part "PTR1B1,27TH"))
    )
    (comp (ref "TP16")
      (value "PTR1B1,27TH")
      (footprint "eagle-import:B1,27TH")
      (libsource (lib "eagle-import") (part "PTR1B1,27TH"))
    )
    (comp (ref "TP17")
      (value "PTR1B1,27TH")
      (footprint "eagle-import:B1,27TH")
      (libsource (lib "eagle-import") (part "PTR1B1,27TH"))
    )
    (comp (ref "TP18")
      (value "PTR1B1,27TH")
      (footprint "eagle-import:B1,27TH")
      (libsource (lib "eagle-import") (part "PTR1B1,27TH"))
    )
    (comp (ref "TP19")
      (value "PTR1B1,27TH")
      (footprint "eagle-import:B1,27TH")
      (libsource (lib "eagle-import") (part "PTR1B1,27TH"))
    )
    (comp (ref "TP20")
      (value "PTR1B1,27")
      (footprint "eagle-import:B1,27")
      (libsource (lib "eagle-import") (part "PTR1B1,27"))
    )
    (comp (ref "TP21")
      (value "PTR1B1,27")
      (footprint "eagle-import:B1,27")
      (libsource (lib "eagle-import") (part "PTR1B1,27"))
    )
    (comp (ref "TP22")
      (value "PTR1B1,27")
      (footprint "eagle-import:B1,27")
      (libsource (lib "eagle-import") (part "PTR1B1,27"))
    )
    (comp (ref "TP23")
      (value "PTR1B1,27")
      (footprint "eagle-import:B1,27")
      (libsource (lib "eagle-import") (part "PTR1B1,27"))
    )
    (comp (ref "TP24")
      (value "GND")
      (footprint "eagle-import:1X01")
      (libsource (lib "eagle-import") (part "PINHD-1X1"))
    )
    (comp (ref "U1")
      (value "ATMEGA32U2-MUR")
      (footprint "eagle-import:QFN32TROUND")
      (libsource (lib "eagle-import") (part "ATMEGA16U2-MU2"))
    )
    (comp (ref "U2")
      (value "ATMEGA2560-16AU")
      (footprint "eagle-import:TQFP100")
      (libsource (lib "eagle-import") (part "ATMEGA2560AU2560-16"))
    )
    (comp (ref "U3")
      (value "LM22675")
      (footprint "eagle-import:SOIC127P600X170-9N")
      (libsource (lib "eagle-import") (part "LM22675"))
    )
    (comp (ref "U4")
      (value "AD5206")
      (footprint "eagle-import:TSSOP24")
      (libsource (lib "eagle-import") (part "AD5206"))
    )
    (comp (ref "U5")
      (value "A4982")
      (footprint "eagle-import:QFN32TROUND")
      (libsource (lib "eagle-import") (part "A4982QFN32ROUNDPADS"))
    )
    (comp (ref "U6")
      (value "A4982")
      (footprint "eagle-import:QFN32TROUND")
      (libsource (lib "eagle-import") (part "A4982QFN32ROUNDPADS"))
    )
    (comp (ref "U7")
      (value "A4982")
      (footprint "eagle-import:QFN32TROUND")
      (libsource (lib "eagle-import") (part "A4982QFN32ROUNDPADS"))
    )
    (comp (ref "U8")
      (value "A4982")
      (footprint "eagle-import:QFN32TROUND")
      (libsource (lib "eagle-import") (part "A4982QFN32ROUNDPADS"))
    )
    (comp (ref "U9")
      (value "A4982")
      (footprint "eagle-import:QFN32TROUND")
      (libsource (lib "eagle-import") (part "A4982QFN32ROUNDPADS"))
    )
    (comp (ref "U10")
      (value "ADUM7441")
      (footprint "eagle-import:QSOP16")
      (libsource (lib "eagle-import") (part "ADUM7441"))
    )
    (comp (ref "X1")
      (value "C-GRID-02-70543")
      (footprint "eagle-import:70543-02")
      (libsource (lib "eagle-import") (part "C-GRID-02-70543"))
    )
    (comp (ref "X2")
      (value "USB B-TH")
      (footprint "eagle-import:PN61729")
      (libsource (lib "eagle-import") (part "PN61729"))
    )
    (comp (ref "X3")
      (value "C-GRID-02-70543")
      (footprint "eagle-import:70543-02")
      (libsource (lib "eagle-import") (part "C-GRID-02-70543"))
    )
    (comp (ref "X4")
      (value "C-GRID-04-70543")
      (footprint "eagle-import:4POL254")
      (libsource (lib "eagle-import") (part "MPT4"))
    )
    (comp (ref "X5")
      (value "C-GRID-02-70543")
      (footprint "eagle-import:70543-02")
      (libsource (lib "eagle-import") (part "C-GRID-02-70543"))
    )
    (comp (ref "X6")
      (value "C-GRID-04-70543")
      (footprint "eagle-import:4POL254")
      (libsource (lib "eagle-import") (part "MPT4"))
    )
    (comp (ref "X7")
      (value "C-GRID-04-70543")
      (footprint "eagle-import:4POL254")
      (libsource (lib "eagle-import") (part "MPT4"))
    )
    (comp (ref "X8")
      (value "C-GRID-04-70543")
      (footprint "eagle-import:4POL254")
      (libsource (lib "eagle-import") (part "MPT4"))
    )
    (comp (ref "X9")
      (value "C-GRID-02-70543")
      (footprint "eagle-import:70543-02")
      (fields (field (name "OC_FARNELL") "unknown") (field (name "OC_NEWARK") "unknown"))
      (libsource (lib "eagle-import") (part "C-GRID-02-70543"))
    )
    (comp (ref "X10")
      (value "C-GRID-04-70543")
      (footprint "eagle-import:70543-04")
      (libsource (lib "eagle-import") (part "C-GRID-04-70543"))
    )
    (comp (ref "X11")
      (value "MSTBV10")
      (footprint "eagle-import:MSTBV10")
      (fields (field (name "MPN") "MSTBV 2,5/10-GF-5.08"))
      (libsource (lib "eagle-import") (part "MSTBV10"))
    )
    (comp (ref "X12")
      (value "SPI")
      (footprint "eagle-import:2X4")
      (libsource (lib "eagle-import") (part "M04X2"))
    )
    (comp (ref "X13")
      (value "EXT-2")
      (footprint "eagle-import:2X10")
      (libsource (lib "eagle-import") (part "M10X2"))
    )
    (comp (ref "X14")
      (value "C-GRID-04-70543")
      (footprint "eagle-import:4POL254")
      (libsource (lib "eagle-import") (part "MPT4"))
    )
    (comp (ref "X15")
      (value "C-GRID-04-70543")
      (footprint "eagle-import:4POL254")
      (fields (field (name "OC_FARNELL") "unknown") (field (name "OC_NEWARK") "unknown"))
      (libsource (lib "eagle-import") (part "MPT4"))
    )
    (comp (ref "X16")
      (value "32u2 EXT")
      (footprint "eagle-import:2X8")
      (libsource (lib "eagle-import") (part "M08X2"))
    )
    (comp (ref "X17")
      (value "3x2M")
      (footprint "eagle-import:2X03")
      (libsource (lib "eagle-import") (part "PINHD-2X3"))
    )
    (comp (ref "X18")
      (value "3x2M")
      (footprint "eagle-import:2X03")
      (libsource (lib "eagle-import") (part "PINHD-2X3"))
    )
    (comp (ref "X20")
      (value "MX1")
      (footprint "eagle-import:1X05")
      (libsource (lib "eagle-import") (part "M05PTH"))
    )
    (comp (ref "X21")
      (value "C-GRID-03-70543")
      (footprint "eagle-import:70543-03")
      (libsource (lib "eagle-import") (part "C-GRID-03-70543"))
    )
    (comp (ref "X22")
      (value "C-GRID-03-70543")
      (footprint "eagle-import:70543-03")
      (libsource (lib "eagle-import") (part "C-GRID-03-70543"))
    )
    (comp (ref "X23")
      (value "C-GRID-03-70543")
      (footprint "eagle-import:70543-03")
      (libsource (lib "eagle-import") (part "C-GRID-03-70543"))
    )
    (comp (ref "X24")
      (value "C-GRID-03-70543")
      (footprint "eagle-import:70543-03")
      (libsource (lib "eagle-import") (part "C-GRID-03-70543"))
    )
    (comp (ref "X25")
      (value "C-GRID-03-70543")
      (footprint "eagle-import:70543-03")
      (libsource (lib "eagle-import") (part "C-GRID-03-70543"))
    )
    (comp (ref "X26")
      (value "C-GRID-03-70543")
      (footprint "eagle-import:70543-03")
      (libsource (lib "eagle-import") (part "C-GRID-03-70543"))
    )
    (comp (ref "X27")
      (value "C-GRID-02-70543")
      (footprint "eagle-import:70543-02")
      (libsource (lib "eagle-import") (part "C-GRID-02-70543"))
    )
    (comp (ref "X28")
      (value "C-GRID-02-70543")
      (footprint "eagle-import:70543-02")
      (libsource (lib "eagle-import") (part "C-GRID-02-70543"))
    )
    (comp (ref "X29")
      (value "C-GRID-02-70543")
      (footprint "eagle-import:70543-02")
      (libsource (lib "eagle-import") (part "C-GRID-02-70543"))
    )
    (comp (ref "X30")
      (value "C-GRID-02-70543")
      (footprint "eagle-import:70543-02")
      (libsource (lib "eagle-import") (part "C-GRID-02-70543"))
    )
    (comp (ref "X31")
      (value "MX2")
      (footprint "eagle-import:1X05")
      (libsource (lib "eagle-import") (part "M05PTH"))
    )
    (comp (ref "X32")
      (value "MX3")
      (footprint "eagle-import:1X05")
      (libsource (lib "eagle-import") (part "M05PTH"))
    )
    (comp (ref "X33")
      (value "MSTBA6")
      (footprint "eagle-import:MSTBA6")
      (fields (field (name "MF") "FARNELL") (field (name "MPN") "1757284"))
      (libsource (lib "eagle-import") (part "MSTBA6"))
    )
    (comp (ref "X34")
      (value "PWM_EXT")
      (footprint "eagle-import:1X06")
      (libsource (lib "eagle-import") (part "M06SIP"))
    )
    (comp (ref "X35")
      (value "M02PTH")
      (footprint "eagle-import:1X02")
      (libsource (lib "eagle-import") (part "M02PTH"))
    )
    (comp (ref "X36")
      (value "M02PTH")
      (footprint "eagle-import:1X02")
      (libsource (lib "eagle-import") (part "M02PTH"))
    )
    (comp (ref "X37")
      (value "M02PTH")
      (footprint "eagle-import:1X02")
      (libsource (lib "eagle-import") (part "M02PTH"))
    )
    (comp (ref "X38")
      (value "M02PTH")
      (footprint "eagle-import:1X02")
      (libsource (lib "eagle-import") (part "M02PTH"))
    )
    (comp (ref "X39")
      (value "M05X2PTH")
      (footprint "eagle-import:AVR_ICSP")
      (libsource (lib "eagle-import") (part "M05X2PTH"))
    )
    (comp (ref "X40")
      (value "Analog")
      (footprint "eagle-import:2X4")
      (libsource (lib "eagle-import") (part "M04X2"))
    )
    (comp (ref "Y1")
      (value "16MHz KX-7")
      (footprint "eagle-import:CRYSTAL-3.2-2.5")
      (libsource (lib "eagle-import") (part "CRYSTAL-3.2-2.5"))
    )
    (comp (ref "Y2")
      (value "16MHz KX-7")
      (footprint "eagle-import:CRYSTAL-3.2-2.5")
      (libsource (lib "eagle-import") (part "CRYSTAL-3.2-2.5"))
    )
    (comp (ref "Z1")
      (value "CG0603MLC-05E")
      (footprint "eagle-import:R0603")
      (libsource (lib "eagle-import") (part "resistor_R-US_R0603"))
    )
    (comp (ref "Z2")
      (value "CG0603MLC-05E")
      (footprint "eagle-import:R0603")
      (libsource (lib "eagle-import") (part "resistor_R-US_R0603"))
    )
  )
  (nets
    (net (code "1") (name "+12V") (class "Default")
      (node (ref "C27") (pin "1") (pinfunction "1_1") (pintype "passive"))
      (node (ref "C29") (pin "1") (pinfunction "1_1") (pintype "passive"))
      (node (ref "C32") (pin "1") (pinfunction "1_1") (pintype "passive"))
      (node (ref "C34") (pin "1") (pinfunction "1_1") (pintype "passive"))
      (node (ref "C37") (pin "1") (pinfunction "1_1") (pintype "passive"))
      (node (ref "C39") (pin "1") (pinfunction "1_1") (pintype "passive"))
      (node (ref "C42") (pin "1") (pinfunction "1_1") (pintype "passive"))
      (node (ref "C44") (pin "1") (pinfunction "1_1") (pintype "passive"))
      (node (ref "C47") (pin "1") (pinfunction "1_1") (pintype "passive"))
      (node (ref "C49") (pin "1") (pinfunction "1_1") (pintype "passive"))
      (node (ref "C71") (pin "1") (pinfunction "1_1") (pintype "passive"))
      (node (ref "C72") (pin "1") (pinfunction "1_1") (pintype "passive"))
      (node (ref "C73") (pin "1") (pinfunction "1_1") (pintype "passive"))
      (node (ref "C74") (pin "1") (pinfunction "1_1") (pintype "passive"))
      (node (ref "C75") (pin "1") (pinfunction "1_1") (pintype "passive"))
      (node (ref "C76") (pin "+") (pinfunction "+_+") (pintype "passive"))
      (node (ref "D2") (pin "C") (pinfunction "C_C") (pintype "passive"))
      (node (ref "F2") (pin "P$2") (pinfunction "P$2_P$2") (pintype "bidirectional"))
      (node (ref "U5") (pin "22") (pinfunction "VBB_22") (pintype "power_in"))
      (node (ref "U5") (pin "3") (pinfunction "VBB1_3") (pintype "power_in"))
      (node (ref "U6") (pin "22") (pinfunction "VBB_22") (pintype "power_in"))
      (node (ref "U6") (pin "3") (pinfunction "VBB1_3") (pintype "power_in"))
      (node (ref "U7") (pin "22") (pinfunction "VBB_22") (pintype "power_in"))
      (node (ref "U7") (pin "3") (pinfunction "VBB1_3") (pintype "power_in"))
      (node (ref "U8") (pin "22") (pinfunction "VBB_22") (pintype "power_in"))
      (node (ref "U8") (pin "3") (pinfunction "VBB1_3") (pintype "power_in"))
      (node (ref "U9") (pin "22") (pinfunction "VBB_22") (pintype "power_in"))
      (node (ref "U9") (pin "3") (pinfunction "VBB1_3") (pintype "power_in"))
      (node (ref "X30") (pin "2") (pinfunction "S_2") (pintype "passive"))
    )
    (net (code "2") (name "+12V2") (class "Default")
      (node (ref "C40") (pin "1") (pinfunction "1_1") (pintype "passive"))
      (node (ref "C45") (pin "1") (pinfunction "1_1") (pintype "passive"))
      (node (ref "C60") (pin "1") (pinfunction "1_1") (pintype "passive"))
      (node (ref "C65") (pin "+") (pinfunction "+_+") (pintype "passive"))
      (node (ref "D1") (pin "C") (pinfunction "C_C") (pintype "passive"))
      (node (ref "D3") (pin "C") (pinfunction "C_C") (pintype "passive"))
      (node (ref "D6") (pin "C") (pinfunction "C_C") (pintype "passive"))
      (node (ref "D8") (pin "C") (pinfunction "C_C") (pintype "passive"))
      (node (ref "F3") (pin "P$2") (pinfunction "P$2_P$2") (pintype "bidirectional"))
      (node (ref "R3") (pin "2") (pinfunction "2_2") (pintype "passive"))
      (node (ref "R40") (pin "2") (pinfunction "2_2") (pintype "passive"))
      (node (ref "R41") (pin "2") (pinfunction "2_2") (pintype "passive"))
      (node (ref "R50") (pin "2") (pinfunction "2_2") (pintype "passive"))
      (node (ref "R55") (pin "2") (pinfunction "2_2") (pintype "passive"))
      (node (ref "R69") (pin "2") (pinfunction "2_2") (pintype "passive"))
      (node (ref "R73") (pin "2") (pinfunction "2_2") (pintype "passive"))
      (node (ref "U3") (pin "7") (pinfunction "VIN_7") (pintype "power_in"))
      (node (ref "X11") (pin "2") (pinfunction "1_2") (pintype "passive"))
      (node (ref "X11") (pin "4") (pinfunction "1_4") (pintype "passive"))
      (node (ref "X11") (pin "6") (pinfunction "1_6") (pintype "passive"))
      (node (ref "X11") (pin "8") (pinfunction "1_8") (pintype "passive"))
      (node (ref "X35") (pin "2") (pinfunction "2_2") (pintype "passive"))
      (node (ref "X36") (pin "2") (pinfunction "2_2") (pintype "passive"))
      (node (ref "X37") (pin "2") (pinfunction "2_2") (pintype "passive"))
      (node (ref "X9") (pin "2") (pinfunction "S_2") (pintype "passive"))
    )
    (net (code "3") (name "+12V3") (class "Default")
      (node (ref "C54") (pin "1") (pinfunction "1_1") (pintype "passive"))
      (node (ref "C62") (pin "1") (pinfunction "1_1") (pintype "passive"))
      (node (ref "C66") (pin "+") (pinfunction "+_+") (pintype "passive"))
      (node (ref "D10") (pin "C") (pinfunction "C_C") (pintype "passive"))
      (node (ref "D7") (pin "C") (pinfunction "C_C") (pintype "passive"))
      (node (ref "F4") (pin "P$2") (pinfunction "2_P$2") (pintype "passive"))
      (node (ref "R58") (pin "2") (pinfunction "2_2") (pintype "passive"))
      (node (ref "X11") (pin "10") (pinfunction "1_10") (pintype "passive"))
      (node (ref "X38") (pin "2") (pinfunction "2_2") (pintype "passive"))
    )
    (net (code "4") (name "/AREF") (class "Default")
      (node (ref "C6") (pin "1") (pinfunction "1_1") (pintype "passive"))
      (node (ref "U2") (pin "98") (pinfunction "AREF_98") (pintype "bidirectional"))
    )
    (net (code "5") (name "/BED-HEAT") (class "Default")
      (node (ref "R56") (pin "1") (pinfunction "1_1") (pintype "passive"))
      (node (ref "R57") (pin "1") (pinfunction "1_1") (pintype "passive"))
      (node (ref "U2") (pin "7") (pinfunction "(OC3C/INT5)PE5_7") (pintype "bidirectional"))
    )
    (net (code "6") (name "/D+") (class "Default")
      (node (ref "R2") (pin "1") (pinfunction "1_1") (pintype "passive"))
      (node (ref "X2") (pin "3") (pinfunction "3_3") (pintype "bidirectional"))
      (node (ref "Z2") (pin "2") (pinfunction "2_2") (pintype "passive"))
    )
    (net (code "7") (name "/D-") (class "Default")
      (node (ref "R1") (pin "1") (pinfunction "1_1") (pintype "passive"))
      (node (ref "X2") (pin "2") (pinfunction "2_2") (pintype "bidirectional"))
      (node (ref "Z1") (pin "2") (pinfunction "2_2") (pintype "passive"))
    )
    (net (code "8") (name "/DP-SS") (class "Default")
      (node (ref "U2") (pin "50") (pinfunction "(T0)PD7_50") (pintype "bidirectional"))
      (node (ref "U4") (pin "P05") (pinfunction "_CS_P05") (pintype "bidirectional"))
    )
    (net (code "9") (name "/DTR") (class "Default")
      (node (ref "JP2") (pin "1") (pinfunction "1_1") (pintype "passive"))
      (node (ref "JP2") (pin "2") (pinfunction "2_2") (pintype "passive"))
      (node (ref "RN5") (pin "5") (pinfunction "2_5") (pintype "passive"))
      (node (ref "U1") (pin "13") (pinfunction "(CTS/HWB/AIN6/TO/INT7)PD7_13") (pintype "bidirectional"))
      (node (ref "U10") (pin "3") (pinfunction "VIA_3") (pintype "bidirectional"))
    )
    (net (code "10") (name "/E0-DIR") (class "Default")
      (node (ref "TP11") (pin "TP") (pinfunction "TP_TP") (pintype "input"))
      (node (ref "U2") (pin "41") (pinfunction "PL6_41") (pintype "bidirectional"))
      (node (ref "U8") (pin "20") (pinfunction "DIR_20") (pintype "input"))
    )
    (net (code "11") (name "/E0-EN") (class "Default")
      (node (ref "R62") (pin "2") (pinfunction "2_2") (pintype "passive"))
      (node (ref "TP14") (pin "TP") (pinfunction "TP_TP") (pintype "input"))
      (node (ref "U2") (pin "74") (pinfunction "(AD4)PA4_74") (pintype "bidirectional"))
      (node (ref "U8") (pin "5") (pinfunction "EN_5") (pintype "input"))
    )
    (net (code "12") (name "/E0-MS1") (class "Default")
      (node (ref "U2") (pin "86") (pinfunction "PK3(ADC11/PCINT19)_86") (pintype "bidirectional"))
      (node (ref "U8") (pin "11") (pinfunction "MS1_11") (pintype "input"))
    )
    (net (code "13") (name "/E0-MS2") (class "Default")
      (node (ref "U2") (pin "85") (pinfunction "PK4(ADC12/PCINT20)_85") (pintype "bidirectional"))
      (node (ref "U8") (pin "12") (pinfunction "MS2_12") (pintype "input"))
    )
    (net (code "14") (name "/E0-REF") (class "Default")
      (node (ref "TP12") (pin "TP") (pinfunction "TP_TP") (pintype "input"))
      (node (ref "U4") (pin "P17") (pinfunction "W1_P17") (pintype "bidirectional"))
      (node (ref "U8") (pin "18") (pinfunction "REF_18") (pintype "input"))
    )
    (net (code "15") (name "/E0-STEP") (class "Default")
      (node (ref "TP13") (pin "TP") (pinfunction "TP_TP") (pintype "input"))
      (node (ref "U2") (pin "56") (pinfunction "(A11)PC3_56") (pintype "bidirectional"))
      (node (ref "U8") (pin "17") (pinfunction "STEP_17") (pintype "input"))
    )
    (net (code "16") (name "/E1-DIR") (class "Default")
      (node (ref "TP15") (pin "TP") (pinfunction "TP_TP") (pintype "input"))
      (node (ref "U2") (pin "42") (pinfunction "PL7_42") (pintype "bidirectional"))
      (node (ref "U9") (pin "20") (pinfunction "DIR_20") (pintype "input"))
    )
    (net (code "17") (name "/E1-EN") (class "Default")
      (node (ref "R63") (pin "2") (pinfunction "2_2") (pintype "passive"))
      (node (ref "TP18") (pin "TP") (pinfunction "TP_TP") (pintype "input"))
      (node (ref "U2") (pin "75") (pinfunction "(AD3)PA3_75") (pintype "bidirectional"))
      (node (ref "U9") (pin "5") (pinfunction "EN_5") (pintype "input"))
    )
    (net (code "18") (name "/E1-MS1") (class "Default")
      (node (ref "U2") (pin "88") (pinfunction "PK1(ADC9/PCINT17)_88") (pintype "bidirectional"))
      (node (ref "U9") (pin "11") (pinfunction "MS1_11") (pintype "input"))
    )
    (net (code "19") (name "/E1-MS2") (class "Default")
      (node (ref "U2") (pin "87") (pinfunction "PK2(ADC10/PCINT18)_87") (pintype "bidirectional"))
      (node (ref "U9") (pin "12") (pinfunction "MS2_12") (pintype "input"))
    )
    (net (code "20") (name "/E1-REF") (class "Default")
      (node (ref "TP17") (pin "TP") (pinfunction "TP_TP") (pintype "input"))
      (node (ref "U4") (pin "P20") (pinfunction "W2_P20") (pintype "bidirectional"))
      (node (ref "U9") (pin "18") (pinfunction "REF_18") (pintype "input"))
    )
    (net (code "21") (name "/E1-STEP") (class "Default")
      (node (ref "TP16") (pin "TP") (pinfunction "TP_TP") (pintype "input"))
      (node (ref "U2") (pin "57") (pinfunction "(A12)PC4_57") (pintype "bidirectional"))
      (node (ref "U9") (pin "17") (pinfunction "STEP_17") (pintype "input"))
    )
    (net (code "22") (name "/FAN-0") (class "Default")
      (node (ref "R48") (pin "1") (pinfunction "1_1") (pintype "passive"))
      (node (ref "R49") (pin "1") (pinfunction "1_1") (pintype "passive"))
      (node (ref "U2") (pin "17") (pinfunction "PH5(OC4C)_17") (pintype "bidirectional"))
    )
    (net (code "23") (name "/FAN-1") (class "Default")
      (node (ref "R53") (pin "1") (pinfunction "1_1") (pintype "passive"))
      (node (ref "R54") (pin "1") (pinfunction "1_1") (pintype "passive"))
      (node (ref "U2") (pin "15") (pinfunction "PH3(OC4A)_15") (pintype "bidirectional"))
    )
    (net (code "24") (name "/FAN-2") (class "Default")
      (node (ref "R70") (pin "1") (pinfunction "1_1") (pintype "passive"))
      (node (ref "R71") (pin "1") (pinfunction "1_1") (pintype "passive"))
      (node (ref "U2") (pin "6") (pinfunction "(OC3B/INT4)PE4_6") (pintype "bidirectional"))
      (node (ref "X34") (pin "4") (pinfunction "4_4") (pintype "passive"))
    )
    (net (code "25") (name "/HEAT-0") (class "Default")
      (node (ref "R42") (pin "1") (pinfunction "1_1") (pintype "passive"))
      (node (ref "R43") (pin "1") (pinfunction "1_1") (pintype "passive"))
      (node (ref "U2") (pin "18") (pinfunction "PH6(OC2B)_18") (pintype "bidirectional"))
    )
    (net (code "26") (name "/HEAT-1") (class "Default")
      (node (ref "R51") (pin "1") (pinfunction "1_1") (pintype "passive"))
      (node (ref "R52") (pin "1") (pinfunction "1_1") (pintype "passive"))
      (node (ref "U2") (pin "16") (pinfunction "PH4(OC4B)_16") (pintype "bidirectional"))
    )
    (net (code "27") (name "/L13") (class "Default")
      (node (ref "R33") (pin "1") (pinfunction "1_1") (pintype "passive"))
      (node (ref "U2") (pin "26") (pinfunction "(OC0A/OC1C/PCINT7)PB7_26") (pintype "bidirectional"))
      (node (ref "X34") (pin "3") (pinfunction "3_3") (pintype "passive"))
    )
    (net (code "28") (name "/MISO2") (class "Default")
      (node (ref "U1") (pin "17") (pinfunction "(PD0/MISO/PCINT3)PB3_17") (pintype "bidirectional"))
      (node (ref "X17") (pin "1") (pinfunction "1_1") (pintype "passive"))
    )
    (net (code "29") (name "/MOSI2") (class "Default")
      (node (ref "U1") (pin "16") (pinfunction "(PDI/MOSI/PCINT2)PB2_16") (pintype "bidirectional"))
      (node (ref "X17") (pin "4") (pinfunction "4_4") (pintype "passive"))
    )
    (net (code "30") (name "/N$96") (class "Default")
      (node (ref "U4") (pin "P14") (pinfunction "W3_P14") (pintype "bidirectional"))
    )
    (net (code "31") (name "/OVREF") (class "Default")
      (node (ref "D11") (pin "C") (pinfunction "C_C") (pintype "passive"))
      (node (ref "D12") (pin "C") (pinfunction "C_C") (pintype "passive"))
      (node (ref "D14") (pin "C") (pinfunction "C_C") (pintype "passive"))
      (node (ref "D16") (pin "C") (pinfunction "C_C") (pintype "passive"))
      (node (ref "D18") (pin "C") (pinfunction "C_C") (pintype "passive"))
      (node (ref "R73") (pin "1") (pinfunction "1_1") (pintype "passive"))
    )
    (net (code "32") (name "/PA0") (class "Default")
      (node (ref "U2") (pin "78") (pinfunction "(AD0)PA0_78") (pintype "bidirectional"))
      (node (ref "X20") (pin "3") (pinfunction "3_3") (pintype "passive"))
    )
    (net (code "33") (name "/PA1") (class "Default")
      (node (ref "U2") (pin "77") (pinfunction "(AD1)PA1_77") (pintype "bidirectional"))
      (node (ref "X25") (pin "1") (pinfunction "S_1") (pintype "passive"))
      (node (ref "X31") (pin "3") (pinfunction "3_3") (pintype "passive"))
    )
    (net (code "34") (name "/PA2") (class "Default")
      (node (ref "U2") (pin "76") (pinfunction "(AD2)PA2_76") (pintype "bidirectional"))
      (node (ref "X26") (pin "1") (pinfunction "S_1") (pintype "passive"))
      (node (ref "X32") (pin "3") (pinfunction "3_3") (pintype "passive"))
    )
    (net (code "35") (name "/PB0_SS") (class "Default")
      (node (ref "U2") (pin "19") (pinfunction "(SS/PCINT0)PB0_19") (pintype "bidirectional"))
      (node (ref "X12") (pin "6") (pinfunction "6_6") (pintype "passive"))
    )
    (net (code "36") (name "/PB1_SCK") (class "Default")
      (node (ref "U2") (pin "20") (pinfunction "(SCK/PCINT1)PB1_20") (pintype "bidirectional"))
      (node (ref "U4") (pin "P08") (pinfunction "SCK_P08") (pintype "bidirectional"))
      (node (ref "X12") (pin "5") (pinfunction "5_5") (pintype "passive"))
      (node (ref "X18") (pin "3") (pinfunction "3_3") (pintype "passive"))
    )
    (net (code "37") (name "/PB2_MOSI") (class "Default")
      (node (ref "U2") (pin "21") (pinfunction "(MOSI/PCINT2)PB2_21") (pintype "bidirectional"))
      (node (ref "U4") (pin "P07") (pinfunction "SDI_P07") (pintype "bidirectional"))
      (node (ref "X12") (pin "4") (pinfunction "4_4") (pintype "passive"))
      (node (ref "X18") (pin "4") (pinfunction "4_4") (pintype "passive"))
    )
    (net (code "38") (name "/PB3_MISO") (class "Default")
      (node (ref "U2") (pin "22") (pinfunction "(MISO/PCINT3)PB3_22") (pintype "bidirectional"))
      (node (ref "X12") (pin "3") (pinfunction "3_3") (pintype "passive"))
      (node (ref "X18") (pin "1") (pinfunction "1_1") (pintype "passive"))
    )
    (net (code "39") (name "/PC5") (class "Default")
      (node (ref "U2") (pin "58") (pinfunction "(A13)PC5_58") (pintype "bidirectional"))
      (node (ref "X20") (pin "4") (pinfunction "4_4") (pintype "passive"))
    )
    (net (code "40") (name "/PC6") (class "Default")
      (node (ref "U2") (pin "59") (pinfunction "(A14)PC6_59") (pintype "bidirectional"))
      (node (ref "X31") (pin "4") (pinfunction "4_4") (pintype "passive"))
    )
    (net (code "41") (name "/PC7") (class "Default")
      (node (ref "U2") (pin "60") (pinfunction "(A15)PC7_60") (pintype "bidirectional"))
      (node (ref "X24") (pin "1") (pinfunction "S_1") (pintype "passive"))
      (node (ref "X32") (pin "4") (pinfunction "4_4") (pintype "passive"))
    )
    (net (code "42") (name "/PD4") (class "Default")
      (node (ref "U2") (pin "47") (pinfunction "(ICP1)PD4_47") (pintype "bidirectional"))
      (node (ref "X13") (pin "14") (pinfunction "14_14") (pintype "passive"))
    )
    (net (code "43") (name "/PD5") (class "Default")
      (node (ref "U2") (pin "48") (pinfunction "(XCK1)PD5_48") (pintype "bidirectional"))
      (node (ref "X13") (pin "12") (pinfunction "12_12") (pintype "passive"))
    )
    (net (code "44") (name "/PD6") (class "Default")
      (node (ref "U2") (pin "49") (pinfunction "(T1)PD6_49") (pintype "bidirectional"))
      (node (ref "X13") (pin "10") (pinfunction "10_10") (pintype "passive"))
    )
    (net (code "45") (name "/PE2") (class "Default")
      (node (ref "U2") (pin "4") (pinfunction "(XCK0/AIN0)PE2_4") (pintype "bidirectional"))
      (node (ref "X13") (pin "20") (pinfunction "20_20") (pintype "passive"))
    )
    (net (code "46") (name "/PE3") (class "Default")
      (node (ref "U2") (pin "5") (pinfunction "(OC3A/AIN1)PE3_5") (pintype "bidirectional"))
      (node (ref "X34") (pin "5") (pinfunction "5_5") (pintype "passive"))
    )
    (net (code "47") (name "/PE6") (class "Default")
      (node (ref "U2") (pin "8") (pinfunction "(T3/INT6)PE6_8") (pintype "bidirectional"))
      (node (ref "X13") (pin "18") (pinfunction "18_18") (pintype "passive"))
    )
    (net (code "48") (name "/PE7") (class "Default")
      (node (ref "U2") (pin "9") (pinfunction "(CLKO/ICP3/INT7)PE7_9") (pintype "bidirectional"))
      (node (ref "X13") (pin "16") (pinfunction "16_16") (pintype "passive"))
    )
    (net (code "49") (name "/PF3") (class "Default")
      (node (ref "U2") (pin "94") (pinfunction "(ADC3)PF3_94") (pintype "bidirectional"))
      (node (ref "X40") (pin "4") (pinfunction "4_4") (pintype "passive"))
    )
    (net (code "50") (name "/PF4") (class "Default")
      (node (ref "U2") (pin "93") (pinfunction "(ADC4/TCK)PF4_93") (pintype "bidirectional"))
      (node (ref "X40") (pin "6") (pinfunction "6_6") (pintype "passive"))
    )
    (net (code "51") (name "/PF5") (class "Default")
      (node (ref "U2") (pin "92") (pinfunction "(ADC5/TMS)PF5_92") (pintype "bidirectional"))
      (node (ref "X40") (pin "8") (pinfunction "8_8") (pintype "passive"))
    )
    (net (code "52") (name "/PF6") (class "Default")
      (node (ref "U2") (pin "91") (pinfunction "(ADC6/TDO)PF6_91") (pintype "bidirectional"))
      (node (ref "X40") (pin "3") (pinfunction "3_3") (pintype "passive"))
    )
    (net (code "53") (name "/PG3") (class "Default")
      (node (ref "U2") (pin "28") (pinfunction "(TOSC2)PG3_28") (pintype "bidirectional"))
      (node (ref "X13") (pin "7") (pinfunction "7_7") (pintype "passive"))
    )
    (net (code "54") (name "/PG4") (class "Default")
      (node (ref "U2") (pin "29") (pinfunction "(TOSC1)PG4_29") (pintype "bidirectional"))
      (node (ref "X13") (pin "5") (pinfunction "5_5") (pintype "passive"))
    )
    (net (code "55") (name "/PG5") (class "Default")
      (node (ref "U2") (pin "1") (pinfunction "(OC0B)PG5_1") (pintype "bidirectional"))
      (node (ref "X34") (pin "6") (pinfunction "6_6") (pintype "passive"))
      (node (ref "X5") (pin "1") (pinfunction "S_1") (pintype "passive"))
    )
    (net (code "56") (name "/PH2") (class "Default")
      (node (ref "U2") (pin "14") (pinfunction "PH2(XCK2)_14") (pintype "bidirectional"))
      (node (ref "X13") (pin "8") (pinfunction "8_8") (pintype "passive"))
    )
    (net (code "57") (name "/PH7") (class "Default")
      (node (ref "U2") (pin "27") (pinfunction "PH7(T4)_27") (pintype "bidirectional"))
      (node (ref "X13") (pin "6") (pinfunction "6_6") (pintype "passive"))
    )
    (net (code "58") (name "/PJ2") (class "Default")
      (node (ref "U2") (pin "65") (pinfunction "PJ2(XCK3/PCINT11)_65") (pintype "bidirectional"))
      (node (ref "X13") (pin "9") (pinfunction "9_9") (pintype "passive"))
    )
    (net (code "59") (name "/PJ3") (class "Default")
      (node (ref "U2") (pin "66") (pinfunction "PJ3(PCINT12)_66") (pintype "bidirectional"))
      (node (ref "X13") (pin "11") (pinfunction "11_11") (pintype "passive"))
    )
    (net (code "60") (name "/PJ4") (class "Default")
      (node (ref "U2") (pin "67") (pinfunction "PJ4(PCINT13)_67") (pintype "bidirectional"))
      (node (ref "X13") (pin "15") (pinfunction "15_15") (pintype "passive"))
    )
    (net (code "61") (name "/PJ5") (class "Default")
      (node (ref "U2") (pin "68") (pinfunction "PJ5(PCINT14)_68") (pintype "bidirectional"))
      (node (ref "X13") (pin "17") (pinfunction "17_17") (pintype "passive"))
    )
    (net (code "62") (name "/PJ6") (class "Default")
      (node (ref "U2") (pin "69") (pinfunction "PJ6(PCINT15)_69") (pintype "bidirectional"))
      (node (ref "X13") (pin "19") (pinfunction "19_19") (pintype "passive"))
    )
    (net (code "63") (name "/PJ7") (class "Default")
      (node (ref "U2") (pin "79") (pinfunction "PJ7_79") (pintype "bidirectional"))
      (node (ref "X13") (pin "13") (pinfunction "13_13") (pintype "passive"))
    )
    (net (code "64") (name "/PK0") (class "Default")
      (node (ref "U2") (pin "89") (pinfunction "PK0(ADC8/PCINT16)_89") (pintype "bidirectional"))
      (node (ref "X40") (pin "7") (pinfunction "7_7") (pintype "passive"))
    )
    (net (code "65") (name "/PL3") (class "Default")
      (node (ref "U2") (pin "38") (pinfunction "PL3(OC5A)_38") (pintype "bidirectional"))
      (node (ref "X12") (pin "2") (pinfunction "2_2") (pintype "passive"))
      (node (ref "X32") (pin "5") (pinfunction "5_5") (pintype "passive"))
    )
    (net (code "66") (name "/PL4") (class "Default")
      (node (ref "U2") (pin "39") (pinfunction "PL4(OC5B)_39") (pintype "bidirectional"))
      (node (ref "X31") (pin "5") (pinfunction "5_5") (pintype "passive"))
    )
    (net (code "67") (name "/PL5") (class "Default")
      (node (ref "U2") (pin "40") (pinfunction "PL5(OC5C)_40") (pintype "bidirectional"))
      (node (ref "X20") (pin "5") (pinfunction "5_5") (pintype "passive"))
    )
    (net (code "68") (name "/RD+") (class "Default")
      (node (ref "R2") (pin "2") (pinfunction "2_2") (pintype "passive"))
      (node (ref "U1") (pin "29") (pinfunction "D+_29") (pintype "bidirectional"))
    )
    (net (code "69") (name "/RD-") (class "Default")
      (node (ref "R1") (pin "2") (pinfunction "2_2") (pintype "passive"))
      (node (ref "U1") (pin "30") (pinfunction "D-_30") (pintype "bidirectional"))
    )
    (net (code "70") (name "/RESET") (class "Default")
      (node (ref "C1") (pin "1") (pinfunction "1_1") (pintype "passive"))
      (node (ref "C10") (pin "2") (pinfunction "2_2") (pintype "passive"))
      (node (ref "D5") (pin "A") (pinfunction "A_A") (pintype "passive"))
      (node (ref "R46") (pin "1") (pinfunction "1_1") (pintype "passive"))
      (node (ref "S1") (pin "1") (pinfunction "P_1") (pintype "passive"))
      (node (ref "U2") (pin "30") (pinfunction "RESET_30") (pintype "input"))
      (node (ref "X18") (pin "5") (pinfunction "5_5") (pintype "passive"))
    )
    (net (code "71") (name "/RESET2") (class "Default")
      (node (ref "D4") (pin "A") (pinfunction "A_A") (pintype "passive"))
      (node (ref "R47") (pin "1") (pinfunction "1_1") (pintype "passive"))
      (node (ref "U1") (pin "24") (pinfunction "RESET(PC1/DW)_24") (pintype "input"))
      (node (ref "X17") (pin "5") (pinfunction "5_5") (pintype "passive"))
    )
    (net (code "72") (name "/RST-IO") (class "Default")
      (node (ref "C10") (pin "1") (pinfunction "1_1") (pintype "passive"))
      (node (ref "U10") (pin "14") (pinfunction "VOA_14") (pintype "bidirectional"))
    )
    (net (code "73") (name "/RX0") (class "Default")
      (node (ref "R34") (pin "2") (pinfunction "2_2") (pintype "passive"))
      (node (ref "U2") (pin "2") (pinfunction "(RXD0/PCIN8)PE0_2") (pintype "bidirectional"))
      (node (ref "X39") (pin "3") (pinfunction "3_3") (pintype "passive"))
    )
    (net (code "74") (name "/RX0-I") (class "Default")
      (node (ref "U1") (pin "9") (pinfunction "(TXD1/INT3)PD3_9") (pintype "bidirectional"))
      (node (ref "U10") (pin "5") (pinfunction "VIC_5") (pintype "bidirectional"))
    )
    (net (code "75") (name "/RX1") (class "Default")
      (node (ref "U2") (pin "45") (pinfunction "(RXD1/INT2)PD2_45") (pintype "bidirectional"))
      (node (ref "X39") (pin "5") (pinfunction "5_5") (pintype "passive"))
    )
    (net (code "76") (name "/RX2") (class "Default")
      (node (ref "U2") (pin "12") (pinfunction "PH0(RXD2)_12") (pintype "bidirectional"))
      (node (ref "X39") (pin "7") (pinfunction "7_7") (pintype "passive"))
    )
    (net (code "77") (name "/RX3") (class "Default")
      (node (ref "U2") (pin "63") (pinfunction "PJ0(RXD3/PCINT9)_63") (pintype "bidirectional"))
      (node (ref "X39") (pin "9") (pinfunction "9_9") (pintype "passive"))
    )
    (net (code "78") (name "/RXL") (class "Default")
      (node (ref "LED10") (pin "C") (pinfunction "C_C") (pintype "passive"))
      (node (ref "U1") (pin "10") (pinfunction "(INT5/AIN3)PD4_10") (pintype "bidirectional"))
    )
    (net (code "79") (name "/SCK2") (class "Default")
      (node (ref "U1") (pin "15") (pinfunction "(SCLK/PCINT1)PB1_15") (pintype "bidirectional"))
      (node (ref "X17") (pin "3") (pinfunction "3_3") (pintype "passive"))
    )
    (net (code "80") (name "/SCL") (class "Default")
      (node (ref "R45") (pin "1") (pinfunction "1_1") (pintype "passive"))
      (node (ref "U2") (pin "43") (pinfunction "(SCL/INT0)PD0_43") (pintype "bidirectional"))
      (node (ref "X10") (pin "4") (pinfunction "S_4") (pintype "passive"))
    )
    (net (code "81") (name "/SDA") (class "Default")
      (node (ref "R44") (pin "1") (pinfunction "1_1") (pintype "passive"))
      (node (ref "U2") (pin "44") (pinfunction "(SDA/INT1)PD1_44") (pintype "bidirectional"))
      (node (ref "X10") (pin "3") (pinfunction "S_3") (pintype "passive"))
    )
    (net (code "82") (name "/THERM0") (class "Default")
      (node (ref "C59") (pin "1") (pinfunction "1_1") (pintype "passive"))
      (node (ref "D11") (pin "A") (pinfunction "A_A") (pintype "passive"))
      (node (ref "D13") (pin "C") (pinfunction "C_C") (pintype "passive"))
      (node (ref "R32") (pin "1") (pinfunction "1_1") (pintype "passive"))
      (node (ref "TP20") (pin "TP") (pinfunction "TP_TP") (pintype "input"))
      (node (ref "U2") (pin "97") (pinfunction "(ADC0)PF0_97") (pintype "bidirectional"))
    )
    (net (code "83") (name "/THERM1") (class "Default")
      (node (ref "C56") (pin "1") (pinfunction "1_1") (pintype "passive"))
      (node (ref "D14") (pin "A") (pinfunction "A_A") (pintype "passive"))
      (node (ref "D15") (pin "C") (pinfunction "C_C") (pintype "passive"))
      (node (ref "R37") (pin "1") (pinfunction "1_1") (pintype "passive"))
      (node (ref "TP21") (pin "TP") (pinfunction "TP_TP") (pintype "input"))
      (node (ref "U2") (pin "96") (pinfunction "(ADC1)PF1_96") (pintype "bidirectional"))
    )
    (net (code "84") (name "/THERM2") (class "Default")
      (node (ref "C64") (pin "1") (pinfunction "1_1") (pintype "passive"))
      (node (ref "D16") (pin "A") (pinfunction "A_A") (pintype "passive"))
      (node (ref "D17") (pin "C") (pinfunction "C_C") (pintype "passive"))
      (node (ref "R28") (pin "1") (pinfunction "1_1") (pintype "passive"))
      (node (ref "TP22") (pin "TP") (pinfunction "TP_TP") (pintype "input"))
      (node (ref "U2") (pin "95") (pinfunction "(ADC2)PF2_95") (pintype "bidirectional"))
    )
    (net (code "85") (name "/THERM3") (class "Default")
      (node (ref "C3") (pin "1") (pinfunction "1_1") (pintype "passive"))
      (node (ref "D18") (pin "A") (pinfunction "A_A") (pintype "passive"))
      (node (ref "D19") (pin "C") (pinfunction "C_C") (pintype "passive"))
      (node (ref "R39") (pin "1") (pinfunction "1_1") (pintype "passive"))
      (node (ref "TP23") (pin "TP") (pinfunction "TP_TP") (pintype "input"))
      (node (ref "U2") (pin "90") (pinfunction "(ADC7/TDI)PF7_90") (pintype "bidirectional"))
      (node (ref "X40") (pin "5") (pinfunction "5_5") (pintype "passive"))
    )
    (net (code "86") (name "/TX0") (class "Default")
      (node (ref "U10") (pin "11") (pinfunction "VID_11") (pintype "bidirectional"))
      (node (ref "U2") (pin "3") (pinfunction "(TXD0)PE1_3") (pintype "bidirectional"))
      (node (ref "X39") (pin "4") (pinfunction "4_4") (pintype "passive"))
    )
    (net (code "87") (name "/TX0-I") (class "Default")
      (node (ref "U1") (pin "8") (pinfunction "(RXD1/AIN1/INT2)PD2_8") (pintype "bidirectional"))
      (node (ref "U10") (pin "6") (pinfunction "VOD_6") (pintype "bidirectional"))
    )
    (net (code "88") (name "/TX1") (class "Default")
      (node (ref "U2") (pin "46") (pinfunction "(TXD1/INT3)PD3_46") (pintype "bidirectional"))
      (node (ref "X39") (pin "6") (pinfunction "6_6") (pintype "passive"))
    )
    (net (code "89") (name "/TX2") (class "Default")
      (node (ref "U2") (pin "13") (pinfunction "PH1(TXD2)_13") (pintype "bidirectional"))
      (node (ref "X39") (pin "8") (pinfunction "8_8") (pintype "passive"))
    )
    (net (code "90") (name "/TX3") (class "Default")
      (node (ref "U2") (pin "64") (pinfunction "PJ1(TXD3/PCINT10)_64") (pintype "bidirectional"))
      (node (ref "X39") (pin "10") (pinfunction "10_10") (pintype "passive"))
    )
    (net (code "91") (name "/TXL") (class "Default")
      (node (ref "LED9") (pin "C") (pinfunction "C_C") (pintype "passive"))
      (node (ref "U1") (pin "11") (pinfunction "(XCK/AIN4/PCINT12)PD5_11") (pintype "bidirectional"))
    )
    (net (code "92") (name "/U1-PB0") (class "Default")
      (node (ref "U1") (pin "14") (pinfunction "(SS/PCINT0)PB0_14") (pintype "bidirectional"))
      (node (ref "X16") (pin "7") (pinfunction "7_7") (pintype "passive"))
    )
    (net (code "93") (name "/U1-PB4") (class "Default")
      (node (ref "U1") (pin "18") (pinfunction "(T1/PCINT4)PB4_18") (pintype "bidirectional"))
      (node (ref "X16") (pin "9") (pinfunction "9_9") (pintype "passive"))
    )
    (net (code "94") (name "/U1-PB5") (class "Default")
      (node (ref "U1") (pin "19") (pinfunction "(PCINT5)PB5_19") (pintype "bidirectional"))
      (node (ref "X16") (pin "12") (pinfunction "12_12") (pintype "passive"))
    )
    (net (code "95") (name "/U1-PB6") (class "Default")
      (node (ref "U1") (pin "20") (pinfunction "(PCINT6)PB6_20") (pintype "bidirectional"))
      (node (ref "X16") (pin "11") (pinfunction "11_11") (pintype "passive"))
    )
    (net (code "96") (name "/U1-PB7") (class "Default")
      (node (ref "U1") (pin "21") (pinfunction "(PCINT7/OC0A/OC1C)PB7_21") (pintype "bidirectional"))
      (node (ref "X16") (pin "14") (pinfunction "14_14") (pintype "passive"))
    )
    (net (code "97") (name "/U1-PC2") (class "Default")
      (node (ref "U1") (pin "5") (pinfunction "(AIN2/PCINT11)PC2_5") (pintype "bidirectional"))
      (node (ref "X16") (pin "5") (pinfunction "5_5") (pintype "passive"))
    )
    (net (code "98") (name "/U1-PC4") (class "Default")
      (node (ref "U1") (pin "26") (pinfunction "(PCINT10)PC4_26") (pintype "bidirectional"))
    )
    (net (code "99") (name "/U1-PC5") (class "Default")
      (node (ref "U1") (pin "25") (pinfunction "(PCINT9/OC1B)PC5_25") (pintype "bidirectional"))
      (node (ref "X16") (pin "15") (pinfunction "15_15") (pintype "passive"))
    )
    (net (code "100") (name "/U1-PC6") (class "Default")
      (node (ref "U1") (pin "23") (pinfunction "(OC1A/PCINT8)PC6_23") (pintype "bidirectional"))
      (node (ref "X16") (pin "16") (pinfunction "16_16") (pintype "passive"))
    )
    (net (code "101") (name "/U1-PC7") (class "Default")
      (node (ref "U1") (pin "22") (pinfunction "(INT4/ICP1/CLK0)PC7_22") (pintype "bidirectional"))
      (node (ref "X16") (pin "13") (pinfunction "13_13") (pintype "passive"))
    )
    (net (code "102") (name "/U1-PD0") (class "Default")
      (node (ref "U1") (pin "6") (pinfunction "(OC0B/INT0)PD0_6") (pintype "bidirectional"))
      (node (ref "X16") (pin "10") (pinfunction "10_10") (pintype "passive"))
    )
    (net (code "103") (name "/U1-PD1") (class "Default")
      (node (ref "U1") (pin "7") (pinfunction "(AIN0/INT1)PD1_7") (pintype "bidirectional"))
      (node (ref "X16") (pin "8") (pinfunction "8_8") (pintype "passive"))
    )
    (net (code "104") (name "/U1-PD6") (class "Default")
      (node (ref "U1") (pin "12") (pinfunction "(RTS/AIN5/INT6)PD6_12") (pintype "bidirectional"))
      (node (ref "X16") (pin "6") (pinfunction "6_6") (pintype "passive"))
    )
    (net (code "105") (name "/USBVCC") (class "Default")
      (node (ref "C11") (pin "1") (pinfunction "1_1") (pintype "passive"))
      (node (ref "C14") (pin "1") (pinfunction "1_1") (pintype "passive"))
      (node (ref "C15") (pin "1") (pinfunction "1_1") (pintype "passive"))
      (node (ref "C2") (pin "2") (pinfunction "2_2") (pintype "passive"))
      (node (ref "C67") (pin "2") (pinfunction "2_2") (pintype "passive"))
      (node (ref "C70") (pin "1") (pinfunction "1_1") (pintype "passive"))
      (node (ref "D4") (pin "C") (pinfunction "C_C") (pintype "passive"))
      (node (ref "F1") (pin "1") (pinfunction "1_1") (pintype "passive"))
      (node (ref "R47") (pin "2") (pinfunction "2_2") (pintype "passive"))
      (node (ref "RN5") (pin "2") (pinfunction "1_2") (pintype "passive"))
      (node (ref "RN5") (pin "3") (pinfunction "1_3") (pintype "passive"))
      (node (ref "RN5") (pin "4") (pinfunction "1_4") (pintype "passive"))
      (node (ref "U1") (pin "31") (pinfunction "UVCC_31") (pintype "power_in"))
      (node (ref "U1") (pin "32") (pinfunction "AVCC_32") (pintype "power_in"))
      (node (ref "U1") (pin "4") (pinfunction "VCC_4") (pintype "power_in"))
      (node (ref "U10") (pin "1") (pinfunction "VDD1A_1") (pintype "bidirectional"))
      (node (ref "U10") (pin "7") (pinfunction "VDD1B_7") (pintype "bidirectional"))
      (node (ref "X16") (pin "1") (pinfunction "1_1") (pintype "passive"))
      (node (ref "X16") (pin "2") (pinfunction "2_2") (pintype "passive"))
      (node (ref "X17") (pin "2") (pinfunction "2_2") (pintype "passive"))
    )
    (net (code "106") (name "/USHIELD") (class "Default")
      (node (ref "C63") (pin "1") (pinfunction "1_1") (pintype "passive"))
      (node (ref "R72") (pin "2") (pinfunction "2_2") (pintype "passive"))
      (node (ref "X2") (pin "P$1") (pinfunction "P$1_P$1") (pintype "bidirectional"))
      (node (ref "X2") (pin "P$2") (pinfunction "P$2_P$2") (pintype "bidirectional"))
      (node (ref "Z1") (pin "1") (pinfunction "1_1") (pintype "passive"))
      (node (ref "Z2") (pin "1") (pinfunction "1_1") (pintype "passive"))
    )
    (net (code "107") (name "/VUCAP") (class "Default")
      (node (ref "C16") (pin "1") (pinfunction "1_1") (pintype "passive"))
      (node (ref "U1") (pin "27") (pinfunction "UCAP_27") (pintype "passive"))
    )
    (net (code "108") (name "/X-DIR") (class "Default")
      (node (ref "TP1") (pin "TP") (pinfunction "TP_TP") (pintype "input"))
      (node (ref "U2") (pin "36") (pinfunction "PL1(ICP5)_36") (pintype "bidirectional"))
      (node (ref "U5") (pin "20") (pinfunction "DIR_20") (pintype "input"))
    )
    (net (code "109") (name "/X-EN") (class "Default")
      (node (ref "R60") (pin "2") (pinfunction "2_2") (pintype "passive"))
      (node (ref "TP4") (pin "TP") (pinfunction "TP_TP") (pintype "input"))
      (node (ref "U2") (pin "71") (pinfunction "(AD7)PA7_71") (pintype "bidirectional"))
      (node (ref "U5") (pin "5") (pinfunction "EN_5") (pintype "input"))
    )
    (net (code "110") (name "/X-MIN") (class "Default")
      (node (ref "U2") (pin "25") (pinfunction "(OC1B/PCINT6)PB6_25") (pintype "bidirectional"))
      (node (ref "X23") (pin "1") (pinfunction "S_1") (pintype "passive"))
    )
    (net (code "111") (name "/X-MS1") (class "Default")
      (node (ref "U2") (pin "52") (pinfunction "(RD)PG1_52") (pintype "bidirectional"))
      (node (ref "U5") (pin "11") (pinfunction "MS1_11") (pintype "input"))
    )
    (net (code "112") (name "/X-MS2") (class "Default")
      (node (ref "U2") (pin "51") (pinfunction "(WR)PG0_51") (pintype "bidirectional"))
      (node (ref "U5") (pin "12") (pinfunction "MS2_12") (pintype "input"))
    )
    (net (code "113") (name "/X-REF") (class "Default")
      (node (ref "TP3") (pin "TP") (pinfunction "TP_TP") (pintype "input"))
      (node (ref "U4") (pin "P11") (pinfunction "W5_P11") (pintype "bidirectional"))
      (node (ref "U5") (pin "18") (pinfunction "REF_18") (pintype "input"))
    )
    (net (code "114") (name "/X-STEP") (class "Default")
      (node (ref "TP2") (pin "TP") (pinfunction "TP_TP") (pintype "input"))
      (node (ref "U2") (pin "53") (pinfunction "(A8)PC0_53") (pintype "bidirectional"))
      (node (ref "U5") (pin "17") (pinfunction "STEP_17") (pintype "input"))
    )
    (net (code "115") (name "/XVCC") (class "Default")
      (node (ref "F1") (pin "2") (pinfunction "2_2") (pintype "passive"))
      (node (ref "X2") (pin "1") (pinfunction "1_1") (pintype "bidirectional"))
    )
    (net (code "116") (name "/Y-DIR") (class "Default")
      (node (ref "TP0") (pin "TP") (pinfunction "TP_TP") (pintype "input"))
      (node (ref "U2") (pin "35") (pinfunction "PL0(ICP4)_35") (pintype "bidirectional"))
      (node (ref "U6") (pin "20") (pinfunction "DIR_20") (pintype "input"))
    )
    (net (code "117") (name "/Y-EN") (class "Default")
      (node (ref "R59") (pin "2") (pinfunction "2_2") (pintype "passive"))
      (node (ref "TP7") (pin "TP") (pinfunction "TP_TP") (pintype "input"))
      (node (ref "U2") (pin "72") (pinfunction "(AD6)PA6_72") (pintype "bidirectional"))
      (node (ref "U6") (pin "5") (pinfunction "EN_5") (pintype "input"))
    )
    (net (code "118") (name "/Y-MIN") (class "Default")
      (node (ref "U2") (pin "24") (pinfunction "(OC1A/PCINT5)PB5_24") (pintype "bidirectional"))
      (node (ref "X22") (pin "1") (pinfunction "S_1") (pintype "passive"))
    )
    (net (code "119") (name "/Y-MS1") (class "Default")
      (node (ref "U2") (pin "82") (pinfunction "PK7(ADC15/PCINT23)_82") (pintype "bidirectional"))
      (node (ref "U6") (pin "11") (pinfunction "MS1_11") (pintype "input"))
    )
    (net (code "120") (name "/Y-MS2") (class "Default")
      (node (ref "U2") (pin "70") (pinfunction "(ALE)PG2_70") (pintype "bidirectional"))
      (node (ref "U6") (pin "12") (pinfunction "MS2_12") (pintype "input"))
    )
    (net (code "121") (name "/Y-REF") (class "Default")
      (node (ref "TP6") (pin "TP") (pinfunction "TP_TP") (pintype "input"))
      (node (ref "U4") (pin "P02") (pinfunction "W6_P02") (pintype "bidirectional"))
      (node (ref "U6") (pin "18") (pinfunction "REF_18") (pintype "input"))
    )
    (net (code "122") (name "/Y-STEP") (class "Default")
      (node (ref "TP5") (pin "TP") (pinfunction "TP_TP") (pintype "input"))
      (node (ref "U2") (pin "54") (pinfunction "(A9)PC1_54") (pintype "bidirectional"))
      (node (ref "U6") (pin "17") (pinfunction "STEP_17") (pintype "input"))
    )
    (net (code "123") (name "/Z-DIR") (class "Default")
      (node (ref "TP19") (pin "TP") (pinfunction "TP_TP") (pintype "input"))
      (node (ref "U2") (pin "37") (pinfunction "PL2(T5)_37") (pintype "bidirectional"))
      (node (ref "U7") (pin "20") (pinfunction "DIR_20") (pintype "input"))
    )
    (net (code "124") (name "/Z-EN") (class "Default")
      (node (ref "R61") (pin "2") (pinfunction "2_2") (pintype "passive"))
      (node (ref "TP10") (pin "TP") (pinfunction "TP_TP") (pintype "input"))
      (node (ref "U2") (pin "73") (pinfunction "(AD5)PA5_73") (pintype "bidirectional"))
      (node (ref "U7") (pin "5") (pinfunction "EN_5") (pintype "input"))
    )
    (net (code "125") (name "/Z-MIN") (class "Default")
      (node (ref "U2") (pin "23") (pinfunction "(OC2A/PCINT4)PB4_23") (pintype "bidirectional"))
      (node (ref "X21") (pin "1") (pinfunction "S_1") (pintype "passive"))
    )
    (net (code "126") (name "/Z-MS1") (class "Default")
      (node (ref "U2") (pin "83") (pinfunction "PK6(ADC14/PCINT22)_83") (pintype "bidirectional"))
      (node (ref "U7") (pin "11") (pinfunction "MS1_11") (pintype "input"))
    )
    (net (code "127") (name "/Z-MS2") (class "Default")
      (node (ref "U2") (pin "84") (pinfunction "PK5(ADC13/PCINT21)_84") (pintype "bidirectional"))
      (node (ref "U7") (pin "12") (pinfunction "MS2_12") (pintype "input"))
    )
    (net (code "128") (name "/Z-REF") (class "Default")
      (node (ref "TP9") (pin "TP") (pinfunction "TP_TP") (pintype "input"))
      (node (ref "U4") (pin "P23") (pinfunction "W4_P23") (pintype "bidirectional"))
      (node (ref "U7") (pin "18") (pinfunction "REF_18") (pintype "input"))
    )
    (net (code "129") (name "/Z-STEP") (class "Default")
      (node (ref "TP8") (pin "TP") (pinfunction "TP_TP") (pintype "input"))
      (node (ref "U2") (pin "55") (pinfunction "(A10)PC2_55") (pintype "bidirectional"))
      (node (ref "U7") (pin "17") (pinfunction "STEP_17") (pintype "input"))
    )
    (net (code "130") (name "GND") (class "Default")
      (node (ref "C1") (pin "2") (pinfunction "2_2") (pintype "passive"))
      (node (ref "C17") (pin "2") (pinfunction "2_2") (pintype "passive"))
      (node (ref "C18") (pin "2") (pinfunction "2_2") (pintype "passive"))
      (node (ref "C23") (pin "2") (pinfunction "2_2") (pintype "passive"))
      (node (ref "C24") (pin "2") (pinfunction "2_2") (pintype "passive"))
      (node (ref "C25") (pin "2") (pinfunction "2_2") (pintype "passive"))
      (node (ref "C26") (pin "2") (pinfunction "2_2") (pintype "passive"))
      (node (ref "C29") (pin "2") (pinfunction "2_2") (pintype "passive"))
      (node (ref "C3") (pin "2") (pinfunction "2_2") (pintype "passive"))
      (node (ref "C30") (pin "2") (pinfunction "2_2") (pintype "passive"))
      (node (ref "C31") (pin "1") (pinfunction "1_1") (pintype "passive"))
      (node (ref "C34") (pin "2") (pinfunction "2_2") (pintype "passive"))
      (node (ref "C36") (pin "1") (pinfunction "1_1") (pintype "passive"))
      (node (ref "C39") (pin "2") (pinfunction "2_2") (pintype "passive"))
      (node (ref "C4") (pin "2") (pinfunction "2_2") (pintype "passive"))
      (node (ref "C40") (pin "2") (pinfunction "2_2") (pintype "passive"))
      (node (ref "C41") (pin "1") (pinfunction "1_1") (pintype "passive"))
      (node (ref "C44") (pin "2") (pinfunction "2_2") (pintype "passive"))
      (node (ref "C45") (pin "2") (pinfunction "2_2") (pintype "passive"))
      (node (ref "C46") (pin "1") (pinfunction "1_1") (pintype "passive"))
      (node (ref "C49") (pin "2") (pinfunction "2_2") (pintype "passive"))
      (node (ref "C51") (pin "1") (pinfunction "1_1") (pintype "passive"))
      (node (ref "C52") (pin "2") (pinfunction "2_2") (pintype "passive"))
      (node (ref "C53") (pin "2") (pinfunction "2_2") (pintype "passive"))
      (node (ref "C54") (pin "2") (pinfunction "2_2") (pintype "passive"))
      (node (ref "C55") (pin "2") (pinfunction "2_2") (pintype "passive"))
      (node (ref "C56") (pin "2") (pinfunction "2_2") (pintype "passive"))
      (node (ref "C57") (pin "2") (pinfunction "2_2") (pintype "passive"))
      (node (ref "C58") (pin "2") (pinfunction "2_2") (pintype "passive"))
      (node (ref "C59") (pin "2") (pinfunction "2_2") (pintype "passive"))
      (node (ref "C6") (pin "2") (pinfunction "2_2") (pintype "passive"))
      (node (ref "C60") (pin "2") (pinfunction "2_2") (pintype "passive"))
      (node (ref "C62") (pin "2") (pinfunction "2_2") (pintype "passive"))
      (node (ref "C64") (pin "2") (pinfunction "2_2") (pintype "passive"))
      (node (ref "C65") (pin "-") (pinfunction "-_-") (pintype "passive"))
      (node (ref "C66") (pin "-") (pinfunction "-_-") (pintype "passive"))
      (node (ref "C68") (pin "1") (pinfunction "1_1") (pintype "passive"))
      (node (ref "C69") (pin "2") (pinfunction "2_2") (pintype "passive"))
      (node (ref "C7") (pin "2") (pinfunction "2_2") (pintype "passive"))
      (node (ref "C71") (pin "2") (pinfunction "2_2") (pintype "passive"))
      (node (ref "C72") (pin "2") (pinfunction "2_2") (pintype "passive"))
      (node (ref "C73") (pin "2") (pinfunction "2_2") (pintype "passive"))
      (node (ref "C74") (pin "2") (pinfunction "2_2") (pintype "passive"))
      (node (ref "C75") (pin "2") (pinfunction "2_2") (pintype "passive"))
      (node (ref "C76") (pin "-") (pinfunction "-_-") (pintype "passive"))
      (node (ref "C8") (pin "2") (pinfunction "2_2") (pintype "passive"))
      (node (ref "C9") (pin "2") (pinfunction "2_2") (pintype "passive"))
      (node (ref "D12") (pin "A") (pinfunction "A_A") (pintype "passive"))
      (node (ref "D13") (pin "A") (pinfunction "A_A") (pintype "passive"))
      (node (ref "D15") (pin "A") (pinfunction "A_A") (pintype "passive"))
      (node (ref "D17") (pin "A") (pinfunction "A_A") (pintype "passive"))
      (node (ref "D19") (pin "A") (pinfunction "A_A") (pintype "passive"))
      (node (ref "D2") (pin "A") (pinfunction "A_A") (pintype "passive"))
      (node (ref "D20") (pin "A") (pinfunction "A_A") (pintype "passive"))
      (node (ref "D7") (pin "A") (pinfunction "A_A") (pintype "passive"))
      (node (ref "D8") (pin "A") (pinfunction "A_A") (pintype "passive"))
      (node (ref "D9") (pin "A") (pinfunction "A_A") (pintype "passive"))
      (node (ref "H1") (pin "P$1") (pinfunction "P$1_P$1") (pintype "bidirectional"))
      (node (ref "H1") (pin "P$17") (pinfunction "P$1_P$17") (pintype "bidirectional"))
      (node (ref "H1") (pin "P$18") (pinfunction "P$1_P$18") (pintype "bidirectional"))
      (node (ref "H1") (pin "P$19") (pinfunction "P$1_P$19") (pintype "bidirectional"))
      (node (ref "H1") (pin "P$2") (pinfunction "P$1_P$2") (pintype "bidirectional"))
      (node (ref "H1") (pin "P$20") (pinfunction "P$1_P$20") (pintype "bidirectional"))
      (node (ref "H1") (pin "P$21") (pinfunction "P$1_P$21") (pintype "bidirectional"))
      (node (ref "H1") (pin "P$22") (pinfunction "P$1_P$22") (pintype "bidirectional"))
      (node (ref "H1") (pin "P$23") (pinfunction "P$1_P$23") (pintype "bidirectional"))
      (node (ref "H1") (pin "P$24") (pinfunction "P$1_P$24") (pintype "bidirectional"))
      (node (ref "H1") (pin "P$3") (pinfunction "P$1_P$3") (pintype "bidirectional"))
      (node (ref "H1") (pin "P$4") (pinfunction "P$1_P$4") (pintype "bidirectional"))
      (node (ref "H1") (pin "P$5") (pinfunction "P$1_P$5") (pintype "bidirectional"))
      (node (ref "H1") (pin "P$6") (pinfunction "P$1_P$6") (pintype "bidirectional"))
      (node (ref "H1") (pin "P$7") (pinfunction "P$1_P$7") (pintype "bidirectional"))
      (node (ref "H1") (pin "P$8") (pinfunction "P$1_P$8") (pintype "bidirectional"))
      (node (ref "H2") (pin "P$1") (pinfunction "P$1_P$1") (pintype "bidirectional"))
      (node (ref "H2") (pin "P$17") (pinfunction "P$1_P$17") (pintype "bidirectional"))
      (node (ref "H2") (pin "P$18") (pinfunction "P$1_P$18") (pintype "bidirectional"))
      (node (ref "H2") (pin "P$19") (pinfunction "P$1_P$19") (pintype "bidirectional"))
      (node (ref "H2") (pin "P$2") (pinfunction "P$1_P$2") (pintype "bidirectional"))
      (node (ref "H2") (pin "P$20") (pinfunction "P$1_P$20") (pintype "bidirectional"))
      (node (ref "H2") (pin "P$21") (pinfunction "P$1_P$21") (pintype "bidirectional"))
      (node (ref "H2") (pin "P$22") (pinfunction "P$1_P$22") (pintype "bidirectional"))
      (node (ref "H2") (pin "P$23") (pinfunction "P$1_P$23") (pintype "bidirectional"))
      (node (ref "H2") (pin "P$24") (pinfunction "P$1_P$24") (pintype "bidirectional"))
      (node (ref "H2") (pin "P$3") (pinfunction "P$1_P$3") (pintype "bidirectional"))
      (node (ref "H2") (pin "P$4") (pinfunction "P$1_P$4") (pintype "bidirectional"))
      (node (ref "H2") (pin "P$5") (pinfunction "P$1_P$5") (pintype "bidirectional"))
      (node (ref "H2") (pin "P$6") (pinfunction "P$1_P$6") (pintype "bidirectional"))
      (node (ref "H2") (pin "P$7") (pinfunction "P$1_P$7") (pintype "bidirectional"))
      (node (ref "H2") (pin "P$8") (pinfunction "P$1_P$8") (pintype "bidirectional"))
      (node (ref "H3") (pin "P$1") (pinfunction "P$1_P$1") (pintype "bidirectional"))
      (node (ref "H3") (pin "P$17") (pinfunction "P$1_P$17") (pintype "bidirectional"))
      (node (ref "H3") (pin "P$18") (pinfunction "P$1_P$18") (pintype "bidirectional"))
      (node (ref "H3") (pin "P$19") (pinfunction "P$1_P$19") (pintype "bidirectional"))
      (node (ref "H3") (pin "P$2") (pinfunction "P$1_P$2") (pintype "bidirectional"))
      (node (ref "H3") (pin "P$20") (pinfunction "P$1_P$20") (pintype "bidirectional"))
      (node (ref "H3") (pin "P$21") (pinfunction "P$1_P$21") (pintype "bidirectional"))
      (node (ref "H3") (pin "P$22") (pinfunction "P$1_P$22") (pintype "bidirectional"))
      (node (ref "H3") (pin "P$23") (pinfunction "P$1_P$23") (pintype "bidirectional"))
      (node (ref "H3") (pin "P$24") (pinfunction "P$1_P$24") (pintype "bidirectional"))
      (node (ref "H3") (pin "P$3") (pinfunction "P$1_P$3") (pintype "bidirectional"))
      (node (ref "H3") (pin "P$4") (pinfunction "P$1_P$4") (pintype "bidirectional"))
      (node (ref "H3") (pin "P$5") (pinfunction "P$1_P$5") (pintype "bidirectional"))
      (node (ref "H3") (pin "P$6") (pinfunction "P$1_P$6") (pintype "bidirectional"))
      (node (ref "H3") (pin "P$7") (pinfunction "P$1_P$7") (pintype "bidirectional"))
      (node (ref "H3") (pin "P$8") (pinfunction "P$1_P$8") (pintype "bidirectional"))
      (node (ref "H4") (pin "P$1") (pinfunction "P$1_P$1") (pintype "bidirectional"))
      (node (ref "H4") (pin "P$17") (pinfunction "P$1_P$17") (pintype "bidirectional"))
      (node (ref "H4") (pin "P$18") (pinfunction "P$1_P$18") (pintype "bidirectional"))
      (node (ref "H4") (pin "P$19") (pinfunction "P$1_P$19") (pintype "bidirectional"))
      (node (ref "H4") (pin "P$2") (pinfunction "P$1_P$2") (pintype "bidirectional"))
      (node (ref "H4") (pin "P$20") (pinfunction "P$1_P$20") (pintype "bidirectional"))
      (node (ref "H4") (pin "P$21") (pinfunction "P$1_P$21") (pintype "bidirectional"))
      (node (ref "H4") (pin "P$22") (pinfunction "P$1_P$22") (pintype "bidirectional"))
      (node (ref "H4") (pin "P$23") (pinfunction "P$1_P$23") (pintype "bidirectional"))
      (node (ref "H4") (pin "P$24") (pinfunction "P$1_P$24") (pintype "bidirectional"))
      (node (ref "H4") (pin "P$3") (pinfunction "P$1_P$3") (pintype "bidirectional"))
      (node (ref "H4") (pin "P$4") (pinfunction "P$1_P$4") (pintype "bidirectional"))
      (node (ref "H4") (pin "P$5") (pinfunction "P$1_P$5") (pintype "bidirectional"))
      (node (ref "H4") (pin "P$6") (pinfunction "P$1_P$6") (pintype "bidirectional"))
      (node (ref "H4") (pin "P$7") (pinfunction "P$1_P$7") (pintype "bidirectional"))
      (node (ref "H4") (pin "P$8") (pinfunction "P$1_P$8") (pintype "bidirectional"))
      (node (ref "JP3") (pin "1") (pinfunction "1_1") (pintype "passive"))
      (node (ref "LED1") (pin "C") (pinfunction "C_C") (pintype "passive"))
      (node (ref "LED7") (pin "C") (pinfunction "C_C") (pintype "passive"))
      (node (ref "Q1") (pin "1") (pinfunction "S_1") (pintype "passive"))
      (node (ref "Q1") (pin "2") (pinfunction "S_2") (pintype "passive"))
      (node (ref "Q1") (pin "3") (pinfunction "S_3") (pintype "passive"))
      (node (ref "Q2") (pin "1") (pinfunction "S_1") (pintype "passive"))
      (node (ref "Q2") (pin "2") (pinfunction "S_2") (pintype "passive"))
      (node (ref "Q2") (pin "3") (pinfunction "S_3") (pintype "passive"))
      (node (ref "Q3") (pin "1") (pinfunction "S_1") (pintype "passive"))
      (node (ref "Q3") (pin "2") (pinfunction "S_2") (pintype "passive"))
      (node (ref "Q3") (pin "3") (pinfunction "S_3") (pintype "passive"))
      (node (ref "Q4") (pin "2") (pinfunction "S_2") (pintype "passive"))
      (node (ref "Q5") (pin "1") (pinfunction "S_1") (pintype "passive"))
      (node (ref "Q5") (pin "2") (pinfunction "S_2") (pintype "passive"))
      (node (ref "Q5") (pin "3") (pinfunction "S_3") (pintype "passive"))
      (node (ref "Q8") (pin "2") (pinfunction "S_2") (pintype "passive"))
      (node (ref "R10") (pin "2") (pinfunction "2_2") (pintype "passive"))
      (node (ref "R11") (pin "2") (pinfunction "2_2") (pintype "passive"))
      (node (ref "R12") (pin "1") (pinfunction "1_1") (pintype "passive"))
      (node (ref "R14") (pin "2") (pinfunction "2_2") (pintype "passive"))
      (node (ref "R15") (pin "2") (pinfunction "2_2") (pintype "passive"))
      (node (ref "R17") (pin "1") (pinfunction "1_1") (pintype "passive"))
      (node (ref "R18") (pin "1") (pinfunction "1_1") (pintype "passive"))
      (node (ref "R19") (pin "2") (pinfunction "2_2") (pintype "passive"))
      (node (ref "R20") (pin "2") (pinfunction "2_2") (pintype "passive"))
      (node (ref "R22") (pin "1") (pinfunction "1_1") (pintype "passive"))
      (node (ref "R23") (pin "2") (pinfunction "2_2") (pintype "passive"))
      (node (ref "R24") (pin "2") (pinfunction "2_2") (pintype "passive"))
      (node (ref "R26") (pin "1") (pinfunction "1_1") (pintype "passive"))
      (node (ref "R4") (pin "2") (pinfunction "2_2") (pintype "passive"))
      (node (ref "R43") (pin "2") (pinfunction "2_2") (pintype "passive"))
      (node (ref "R49") (pin "2") (pinfunction "2_2") (pintype "passive"))
      (node (ref "R52") (pin "2") (pinfunction "2_2") (pintype "passive"))
      (node (ref "R54") (pin "2") (pinfunction "2_2") (pintype "passive"))
      (node (ref "R57") (pin "2") (pinfunction "2_2") (pintype "passive"))
      (node (ref "R7") (pin "2") (pinfunction "2_2") (pintype "passive"))
      (node (ref "R71") (pin "2") (pinfunction "2_2") (pintype "passive"))
      (node (ref "R8") (pin "2") (pinfunction "2_2") (pintype "passive"))
      (node (ref "S1") (pin "2") (pinfunction "S_2") (pintype "passive"))
      (node (ref "TP24") (pin "1") (pinfunction "1_1") (pintype "passive"))
      (node (ref "U10") (pin "15") (pinfunction "GND2A_15") (pintype "bidirectional"))
      (node (ref "U10") (pin "9") (pinfunction "GND2B_9") (pintype "bidirectional"))
      (node (ref "U2") (pin "11") (pinfunction "GND_11") (pintype "power_in"))
      (node (ref "U2") (pin "32") (pinfunction "GND1_32") (pintype "power_in"))
      (node (ref "U2") (pin "62") (pinfunction "GND2_62") (pintype "power_in"))
      (node (ref "U2") (pin "81") (pinfunction "GND3_81") (pintype "power_in"))
      (node (ref "U2") (pin "99") (pinfunction "AGND_99") (pintype "power_in"))
      (node (ref "U3") (pin "6") (pinfunction "GND_6") (pintype "bidirectional"))
      (node (ref "U3") (pin "9") (pinfunction "PAD_9") (pintype "bidirectional"))
      (node (ref "U4") (pin "P03") (pinfunction "B6_P03") (pintype "bidirectional"))
      (node (ref "U4") (pin "P04") (pinfunction "GND_P04") (pintype "bidirectional"))
      (node (ref "U4") (pin "P09") (pinfunction "VSS_P09") (pintype "bidirectional"))
      (node (ref "U4") (pin "P10") (pinfunction "B5_P10") (pintype "bidirectional"))
      (node (ref "U4") (pin "P13") (pinfunction "B3_P13") (pintype "bidirectional"))
      (node (ref "U4") (pin "P16") (pinfunction "B1_P16") (pintype "bidirectional"))
      (node (ref "U4") (pin "P21") (pinfunction "B2_P21") (pintype "bidirectional"))
      (node (ref "U4") (pin "P24") (pinfunction "B4_P24") (pintype "bidirectional"))
      (node (ref "U5") (pin "19") (pinfunction "GND2_19") (pintype "power_in"))
      (node (ref "U5") (pin "33") (pinfunction "TH-PAD_33") (pintype "power_in"))
      (node (ref "U5") (pin "6") (pinfunction "GND1_6") (pintype "power_in"))
      (node (ref "U6") (pin "19") (pinfunction "GND2_19") (pintype "power_in"))
      (node (ref "U6") (pin "33") (pinfunction "TH-PAD_33") (pintype "power_in"))
      (node (ref "U6") (pin "6") (pinfunction "GND1_6") (pintype "power_in"))
      (node (ref "U7") (pin "19") (pinfunction "GND2_19") (pintype "power_in"))
      (node (ref "U7") (pin "33") (pinfunction "TH-PAD_33") (pintype "power_in"))
      (node (ref "U7") (pin "6") (pinfunction "GND1_6") (pintype "power_in"))
      (node (ref "U8") (pin "19") (pinfunction "GND2_19") (pintype "power_in"))
      (node (ref "U8") (pin "33") (pinfunction "TH-PAD_33") (pintype "power_in"))
      (node (ref "U8") (pin "6") (pinfunction "GND1_6") (pintype "power_in"))
      (node (ref "U9") (pin "19") (pinfunction "GND2_19") (pintype "power_in"))
      (node (ref "U9") (pin "33") (pinfunction "TH-PAD_33") (pintype "power_in"))
      (node (ref "U9") (pin "6") (pinfunction "GND1_6") (pintype "power_in"))
      (node (ref "X1") (pin "1") (pinfunction "S_1") (pintype "passive"))
      (node (ref "X10") (pin "2") (pinfunction "S_2") (pintype "passive"))
      (node (ref "X12") (pin "7") (pinfunction "7_7") (pintype "passive"))
      (node (ref "X13") (pin "3") (pinfunction "3_3") (pintype "passive"))
      (node (ref "X13") (pin "4") (pinfunction "4_4") (pintype "passive"))
      (node (ref "X18") (pin "6") (pinfunction "6_6") (pintype "passive"))
      (node (ref "X20") (pin "2") (pinfunction "2_2") (pintype "passive"))
      (node (ref "X21") (pin "2") (pinfunction "S_2") (pintype "passive"))
      (node (ref "X22") (pin "2") (pinfunction "S_2") (pintype "passive"))
      (node (ref "X23") (pin "2") (pinfunction "S_2") (pintype "passive"))
      (node (ref "X24") (pin "2") (pinfunction "S_2") (pintype "passive"))
      (node (ref "X25") (pin "2") (pinfunction "S_2") (pintype "passive"))
      (node (ref "X26") (pin "2") (pinfunction "S_2") (pintype "passive"))
      (node (ref "X27") (pin "1") (pinfunction "S_1") (pintype "passive"))
      (node (ref "X28") (pin "1") (pinfunction "S_1") (pintype "passive"))
      (node (ref "X29") (pin "1") (pinfunction "S_1") (pintype "passive"))
      (node (ref "X3") (pin "1") (pinfunction "S_1") (pintype "passive"))
      (node (ref "X30") (pin "1") (pinfunction "S_1") (pintype "passive"))
      (node (ref "X31") (pin "2") (pinfunction "2_2") (pintype "passive"))
      (node (ref "X32") (pin "2") (pinfunction "2_2") (pintype "passive"))
      (node (ref "X33") (pin "2") (pinfunction "1_2") (pintype "passive"))
      (node (ref "X33") (pin "4") (pinfunction "1_4") (pintype "passive"))
      (node (ref "X33") (pin "6") (pinfunction "1_6") (pintype "passive"))
      (node (ref "X34") (pin "2") (pinfunction "2_2") (pintype "passive"))
      (node (ref "X39") (pin "2") (pinfunction "2_2") (pintype "passive"))
      (node (ref "X40") (pin "2") (pinfunction "2_2") (pintype "passive"))
      (node (ref "Y1") (pin "2") (pinfunction "GND_2") (pintype "passive"))
      (node (ref "Y1") (pin "4") (pinfunction "GND_4") (pintype "passive"))
    )
    (net (code "131") (name "GND1") (class "Default")
      (node (ref "C11") (pin "2") (pinfunction "2_2") (pintype "passive"))
      (node (ref "C12") (pin "2") (pinfunction "2_2") (pintype "passive"))
      (node (ref "C13") (pin "2") (pinfunction "2_2") (pintype "passive"))
      (node (ref "C14") (pin "2") (pinfunction "2_2") (pintype "passive"))
      (node (ref "C15") (pin "2") (pinfunction "2_2") (pintype "passive"))
      (node (ref "C16") (pin "2") (pinfunction "2_2") (pintype "passive"))
      (node (ref "C2") (pin "1") (pinfunction "1_1") (pintype "passive"))
      (node (ref "C63") (pin "2") (pinfunction "2_2") (pintype "passive"))
      (node (ref "C67") (pin "1") (pinfunction "1_1") (pintype "passive"))
      (node (ref "C70") (pin "2") (pinfunction "2_2") (pintype "passive"))
      (node (ref "R72") (pin "1") (pinfunction "1_1") (pintype "passive"))
      (node (ref "U1") (pin "28") (pinfunction "UGND_28") (pintype "power_in"))
      (node (ref "U1") (pin "3") (pinfunction "GND_3") (pintype "power_in"))
      (node (ref "U1") (pin "33") (pinfunction "PAD_33") (pintype "power_in"))
      (node (ref "U10") (pin "2") (pinfunction "GND1A_2") (pintype "bidirectional"))
      (node (ref "U10") (pin "4") (pinfunction "VIB_4") (pintype "bidirectional"))
      (node (ref "U10") (pin "8") (pinfunction "GND1B_8") (pintype "bidirectional"))
      (node (ref "X16") (pin "3") (pinfunction "3_3") (pintype "passive"))
      (node (ref "X16") (pin "4") (pinfunction "4_4") (pintype "passive"))
      (node (ref "X17") (pin "6") (pinfunction "6_6") (pintype "passive"))
      (node (ref "X2") (pin "4") (pinfunction "4_4") (pintype "bidirectional"))
      (node (ref "Y2") (pin "2") (pinfunction "GND_2") (pintype "passive"))
      (node (ref "Y2") (pin "4") (pinfunction "GND_4") (pintype "passive"))
    )
    (net (code "132") (name "Net-(F2-PadP$1)") (class "Default")
      (node (ref "F2") (pin "P$1") (pinfunction "P$1_P$1") (pintype "bidirectional"))
      (node (ref "X33") (pin "1") (pinfunction "1_1") (pintype "passive"))
    )
    (net (code "133") (name "Net-(F4-1)") (class "Default")
      (node (ref "F4") (pin "P$1") (pinfunction "1_P$1") (pintype "passive"))
      (node (ref "X33") (pin "5") (pinfunction "1_5") (pintype "passive"))
    )
    (net (code "134") (name "Net-(L3-1)") (class "Default")
      (node (ref "C35") (pin "2") (pinfunction "2_2") (pintype "passive"))
      (node (ref "D20") (pin "C") (pinfunction "C_C") (pintype "passive"))
      (node (ref "L3") (pin "P$1") (pinfunction "1_P$1") (pintype "passive"))
      (node (ref "U3") (pin "8") (pinfunction "SWITCH_8") (pintype "bidirectional"))
    )
    (net (code "135") (name "Net-(LED1-PadA)") (class "Default")
      (node (ref "LED1") (pin "A") (pinfunction "A_A") (pintype "passive"))
      (node (ref "R33") (pin "2") (pinfunction "2_2") (pintype "passive"))
    )
    (net (code "136") (name "Net-(LED2-PadA)") (class "Default")
      (node (ref "LED2") (pin "A") (pinfunction "A_A") (pintype "passive"))
      (node (ref "R40") (pin "1") (pinfunction "1_1") (pintype "passive"))
    )
    (net (code "137") (name "Net-(LED3-PadA)") (class "Default")
      (node (ref "LED3") (pin "A") (pinfunction "A_A") (pintype "passive"))
      (node (ref "R50") (pin "1") (pinfunction "1_1") (pintype "passive"))
    )
    (net (code "138") (name "Net-(LED4-PadA)") (class "Default")
      (node (ref "LED4") (pin "A") (pinfunction "A_A") (pintype "passive"))
      (node (ref "R41") (pin "1") (pinfunction "1_1") (pintype "passive"))
    )
    (net (code "139") (name "Net-(LED5-PadA)") (class "Default")
      (node (ref "LED5") (pin "A") (pinfunction "A_A") (pintype "passive"))
      (node (ref "R55") (pin "1") (pinfunction "1_1") (pintype "passive"))
    )
    (net (code "140") (name "Net-(LED6-PadA)") (class "Default")
      (node (ref "LED6") (pin "A") (pinfunction "A_A") (pintype "passive"))
      (node (ref "R58") (pin "1") (pinfunction "1_1") (pintype "passive"))
    )
    (net (code "141") (name "Net-(LED7-PadA)") (class "Default")
      (node (ref "LED7") (pin "A") (pinfunction "A_A") (pintype "passive"))
      (node (ref "R35") (pin "2") (pinfunction "2_2") (pintype "passive"))
    )
    (net (code "142") (name "Net-(LED8-PadA)") (class "Default")
      (node (ref "LED8") (pin "A") (pinfunction "A_A") (pintype "passive"))
      (node (ref "R69") (pin "1") (pinfunction "1_1") (pintype "passive"))
    )
    (net (code "143") (name "Net-(Q1-D)") (class "Default")
      (node (ref "D6") (pin "A") (pinfunction "A_A") (pintype "passive"))
      (node (ref "LED2") (pin "C") (pinfunction "C_C") (pintype "passive"))
      (node (ref "Q1") (pin "MB") (pinfunction "D_MB") (pintype "passive"))
      (node (ref "X11") (pin "1") (pinfunction "1_1") (pintype "passive"))
      (node (ref "X35") (pin "1") (pinfunction "1_1") (pintype "passive"))
    )
    (net (code "144") (name "Net-(Q1-G)") (class "Default")
      (node (ref "Q1") (pin "4") (pinfunction "G_4") (pintype "passive"))
      (node (ref "R42") (pin "2") (pinfunction "2_2") (pintype "passive"))
    )
    (net (code "145") (name "Net-(Q2-D)") (class "Default")
      (node (ref "D3") (pin "A") (pinfunction "A_A") (pintype "passive"))
      (node (ref "LED3") (pin "C") (pinfunction "C_C") (pintype "passive"))
      (node (ref "Q2") (pin "MB") (pinfunction "D_MB") (pintype "passive"))
      (node (ref "X11") (pin "3") (pinfunction "1_3") (pintype "passive"))
      (node (ref "X36") (pin "1") (pinfunction "1_1") (pintype "passive"))
    )
    (net (code "146") (name "Net-(Q2-G)") (class "Default")
      (node (ref "Q2") (pin "4") (pinfunction "G_4") (pintype "passive"))
      (node (ref "R48") (pin "2") (pinfunction "2_2") (pintype "passive"))
    )
    (net (code "147") (name "Net-(Q3-D)") (class "Default")
      (node (ref "D1") (pin "A") (pinfunction "A_A") (pintype "passive"))
      (node (ref "LED4") (pin "C") (pinfunction "C_C") (pintype "passive"))
      (node (ref "Q3") (pin "MB") (pinfunction "D_MB") (pintype "passive"))
      (node (ref "X11") (pin "5") (pinfunction "1_5") (pintype "passive"))
      (node (ref "X37") (pin "1") (pinfunction "1_1") (pintype "passive"))
    )
    (net (code "148") (name "Net-(Q3-G)") (class "Default")
      (node (ref "Q3") (pin "4") (pinfunction "G_4") (pintype "passive"))
      (node (ref "R51") (pin "2") (pinfunction "2_2") (pintype "passive"))
    )
    (net (code "149") (name "Net-(Q4-D)") (class "Default")
      (node (ref "LED5") (pin "C") (pinfunction "C_C") (pintype "passive"))
      (node (ref "Q4") (pin "3") (pinfunction "D_3") (pintype "passive"))
      (node (ref "X11") (pin "7") (pinfunction "1_7") (pintype "passive"))
    )
    (net (code "150") (name "Net-(Q4-G)") (class "Default")
      (node (ref "Q4") (pin "1") (pinfunction "G_1") (pintype "passive"))
      (node (ref "R53") (pin "2") (pinfunction "2_2") (pintype "passive"))
    )
    (net (code "151") (name "Net-(Q5-D)") (class "Default")
      (node (ref "D10") (pin "A") (pinfunction "A_A") (pintype "passive"))
      (node (ref "LED6") (pin "C") (pinfunction "C_C") (pintype "passive"))
      (node (ref "Q5") (pin "MB") (pinfunction "D_MB") (pintype "passive"))
      (node (ref "X11") (pin "9") (pinfunction "1_9") (pintype "passive"))
      (node (ref "X38") (pin "1") (pinfunction "1_1") (pintype "passive"))
    )
    (net (code "152") (name "Net-(Q5-G)") (class "Default")
      (node (ref "Q5") (pin "4") (pinfunction "G_4") (pintype "passive"))
      (node (ref "R56") (pin "2") (pinfunction "2_2") (pintype "passive"))
    )
    (net (code "153") (name "Net-(Q8-D)") (class "Default")
      (node (ref "LED8") (pin "C") (pinfunction "C_C") (pintype "passive"))
      (node (ref "Q8") (pin "3") (pinfunction "D_3") (pintype "passive"))
      (node (ref "X9") (pin "1") (pinfunction "S_1") (pintype "passive"))
    )
    (net (code "154") (name "Net-(Q8-G)") (class "Default")
      (node (ref "Q8") (pin "1") (pinfunction "G_1") (pintype "passive"))
      (node (ref "R70") (pin "2") (pinfunction "2_2") (pintype "passive"))
    )
    (net (code "155") (name "Net-(RN5B-2)") (class "Default")
      (node (ref "LED10") (pin "A") (pinfunction "A_A") (pintype "passive"))
      (node (ref "RN5") (pin "7") (pinfunction "2_7") (pintype "passive"))
    )
    (net (code "156") (name "Net-(RN5C-2)") (class "Default")
      (node (ref "LED9") (pin "A") (pinfunction "A_A") (pintype "passive"))
      (node (ref "RN5") (pin "6") (pinfunction "2_6") (pintype "passive"))
    )
    (net (code "157") (name "Net-(U1-XTAL1)") (class "Default")
      (node (ref "C13") (pin "1") (pinfunction "1_1") (pintype "passive"))
      (node (ref "U1") (pin "1") (pinfunction "XTAL1_1") (pintype "bidirectional"))
      (node (ref "Y2") (pin "1") (pinfunction "C1_1") (pintype "passive"))
    )
    (net (code "158") (name "Net-(U1-XTAL2(PC0))") (class "Default")
      (node (ref "C12") (pin "1") (pinfunction "1_1") (pintype "passive"))
      (node (ref "U1") (pin "2") (pinfunction "XTAL2(PC0)_2") (pintype "bidirectional"))
      (node (ref "Y2") (pin "3") (pinfunction "C2_3") (pintype "passive"))
    )
    (net (code "159") (name "Net-(U2-AVCC)") (class "Default")
      (node (ref "C26") (pin "1") (pinfunction "1_1") (pintype "passive"))
      (node (ref "L2") (pin "2") (pinfunction "2_2") (pintype "passive"))
      (node (ref "U2") (pin "100") (pinfunction "AVCC_100") (pintype "power_in"))
    )
    (net (code "160") (name "Net-(U2-XTAL1)") (class "Default")
      (node (ref "C57") (pin "1") (pinfunction "1_1") (pintype "passive"))
      (node (ref "U2") (pin "34") (pinfunction "XTAL1_34") (pintype "input"))
      (node (ref "Y1") (pin "1") (pinfunction "C1_1") (pintype "passive"))
    )
    (net (code "161") (name "Net-(U2-XTAL2)") (class "Default")
      (node (ref "C58") (pin "1") (pinfunction "1_1") (pintype "passive"))
      (node (ref "U2") (pin "33") (pinfunction "XTAL2_33") (pintype "output"))
      (node (ref "Y1") (pin "3") (pinfunction "C2_3") (pintype "passive"))
    )
    (net (code "162") (name "Net-(U3-BOOT)") (class "Default")
      (node (ref "C35") (pin "1") (pinfunction "1_1") (pintype "passive"))
      (node (ref "U3") (pin "1") (pinfunction "BOOT_1") (pintype "bidirectional"))
    )
    (net (code "163") (name "Net-(U3-ENABLE)") (class "Default")
      (node (ref "JP3") (pin "2") (pinfunction "2_2") (pintype "passive"))
      (node (ref "R3") (pin "1") (pinfunction "1_1") (pintype "passive"))
      (node (ref "U3") (pin "5") (pinfunction "ENABLE_5") (pintype "bidirectional"))
    )
    (net (code "164") (name "Net-(U3-FEEDBACK)") (class "Default")
      (node (ref "R11") (pin "1") (pinfunction "1_1") (pintype "passive"))
      (node (ref "R13") (pin "1") (pinfunction "1_1") (pintype "passive"))
      (node (ref "U3") (pin "4") (pinfunction "FEEDBACK_4") (pintype "bidirectional"))
    )
    (net (code "165") (name "Net-(U4-A1)") (class "Default")
      (node (ref "R30") (pin "2") (pinfunction "2_2") (pintype "passive"))
      (node (ref "U4") (pin "P01") (pinfunction "A6_P01") (pintype "bidirectional"))
      (node (ref "U4") (pin "P12") (pinfunction "A5_P12") (pintype "bidirectional"))
      (node (ref "U4") (pin "P15") (pinfunction "A3_P15") (pintype "bidirectional"))
      (node (ref "U4") (pin "P18") (pinfunction "A1_P18") (pintype "bidirectional"))
      (node (ref "U4") (pin "P19") (pinfunction "A2_P19") (pintype "bidirectional"))
      (node (ref "U4") (pin "P22") (pinfunction "A4_P22") (pintype "bidirectional"))
    )
    (net (code "166") (name "Net-(U5-CP1)") (class "Default")
      (node (ref "C28") (pin "1") (pinfunction "1_1") (pintype "passive"))
      (node (ref "U5") (pin "7") (pinfunction "CP1_7") (pintype "bidirectional"))
    )
    (net (code "167") (name "Net-(U5-CP2)") (class "Default")
      (node (ref "C28") (pin "2") (pinfunction "2_2") (pintype "passive"))
      (node (ref "U5") (pin "8") (pinfunction "CP2_8") (pintype "bidirectional"))
    )
    (net (code "168") (name "Net-(U5-OUT1A)") (class "Default")
      (node (ref "U5") (pin "27") (pinfunction "OUT1A_27") (pintype "output"))
      (node (ref "X8") (pin "3") (pinfunction "1_3") (pintype "passive"))
    )
    (net (code "169") (name "Net-(U5-OUT1B)") (class "Default")
      (node (ref "U5") (pin "24") (pinfunction "OUT1B_24") (pintype "output"))
      (node (ref "X8") (pin "4") (pinfunction "1_4") (pintype "passive"))
    )
    (net (code "170") (name "Net-(U5-OUT2A)") (class "Default")
      (node (ref "U5") (pin "30") (pinfunction "OUT2A_30") (pintype "output"))
      (node (ref "X8") (pin "2") (pinfunction "1_2") (pintype "passive"))
    )
    (net (code "171") (name "Net-(U5-OUT2B)") (class "Default")
      (node (ref "U5") (pin "1") (pinfunction "OUT2B_1") (pintype "output"))
      (node (ref "X8") (pin "1") (pinfunction "1_1") (pintype "passive"))
    )
    (net (code "172") (name "Net-(U5-RESET)") (class "Default")
      (node (ref "C24") (pin "1") (pinfunction "1_1") (pintype "passive"))
      (node (ref "R29") (pin "1") (pinfunction "1_1") (pintype "passive"))
      (node (ref "U5") (pin "13") (pinfunction "RESET_13") (pintype "input"))
      (node (ref "U5") (pin "15") (pinfunction "SLEEP_15") (pintype "input"))
      (node (ref "U5") (pin "16") (pinfunction "VDD_16") (pintype "power_in"))
    )
    (net (code "173") (name "Net-(U5-ROSC)") (class "Default")
      (node (ref "R18") (pin "2") (pinfunction "2_2") (pintype "passive"))
      (node (ref "U5") (pin "14") (pinfunction "ROSC_14") (pintype "input"))
    )
    (net (code "174") (name "Net-(U5-SENSE1)") (class "Default")
      (node (ref "R7") (pin "1") (pinfunction "1_1") (pintype "passive"))
      (node (ref "U5") (pin "25") (pinfunction "SENSE1_25") (pintype "input"))
    )
    (net (code "175") (name "Net-(U5-SENSE2)") (class "Default")
      (node (ref "R4") (pin "1") (pinfunction "1_1") (pintype "passive"))
      (node (ref "U5") (pin "32") (pinfunction "SENSE2_32") (pintype "input"))
    )
    (net (code "176") (name "Net-(U5-VCP)") (class "Default")
      (node (ref "C27") (pin "2") (pinfunction "2_2") (pintype "passive"))
      (node (ref "U5") (pin "9") (pinfunction "VCP_9") (pintype "bidirectional"))
    )
    (net (code "177") (name "Net-(U5-VREG)") (class "Default")
      (node (ref "C31") (pin "2") (pinfunction "2_2") (pintype "passive"))
      (node (ref "U5") (pin "10") (pinfunction "VREG_10") (pintype "input"))
    )
    (net (code "178") (name "Net-(U6-CP1)") (class "Default")
      (node (ref "C33") (pin "1") (pinfunction "1_1") (pintype "passive"))
      (node (ref "U6") (pin "7") (pinfunction "CP1_7") (pintype "bidirectional"))
    )
    (net (code "179") (name "Net-(U6-CP2)") (class "Default")
      (node (ref "C33") (pin "2") (pinfunction "2_2") (pintype "passive"))
      (node (ref "U6") (pin "8") (pinfunction "CP2_8") (pintype "bidirectional"))
    )
    (net (code "180") (name "Net-(U6-OUT1A)") (class "Default")
      (node (ref "U6") (pin "27") (pinfunction "OUT1A_27") (pintype "output"))
      (node (ref "X4") (pin "3") (pinfunction "1_3") (pintype "passive"))
    )
    (net (code "181") (name "Net-(U6-OUT1B)") (class "Default")
      (node (ref "U6") (pin "24") (pinfunction "OUT1B_24") (pintype "output"))
      (node (ref "X4") (pin "4") (pinfunction "1_4") (pintype "passive"))
    )
    (net (code "182") (name "Net-(U6-OUT2A)") (class "Default")
      (node (ref "U6") (pin "30") (pinfunction "OUT2A_30") (pintype "output"))
      (node (ref "X4") (pin "2") (pinfunction "1_2") (pintype "passive"))
    )
    (net (code "183") (name "Net-(U6-OUT2B)") (class "Default")
      (node (ref "U6") (pin "1") (pinfunction "OUT2B_1") (pintype "output"))
      (node (ref "X4") (pin "1") (pinfunction "1_1") (pintype "passive"))
    )
    (net (code "184") (name "Net-(U6-RESET)") (class "Default")
      (node (ref "C23") (pin "1") (pinfunction "1_1") (pintype "passive"))
      (node (ref "R65") (pin "1") (pinfunction "1_1") (pintype "passive"))
      (node (ref "U6") (pin "13") (pinfunction "RESET_13") (pintype "input"))
      (node (ref "U6") (pin "15") (pinfunction "SLEEP_15") (pintype "input"))
      (node (ref "U6") (pin "16") (pinfunction "VDD_16") (pintype "power_in"))
    )
    (net (code "185") (name "Net-(U6-ROSC)") (class "Default")
      (node (ref "R12") (pin "2") (pinfunction "2_2") (pintype "passive"))
      (node (ref "U6") (pin "14") (pinfunction "ROSC_14") (pintype "input"))
    )
    (net (code "186") (name "Net-(U6-SENSE1)") (class "Default")
      (node (ref "R10") (pin "1") (pinfunction "1_1") (pintype "passive"))
      (node (ref "U6") (pin "25") (pinfunction "SENSE1_25") (pintype "input"))
    )
    (net (code "187") (name "Net-(U6-SENSE2)") (class "Default")
      (node (ref "R8") (pin "1") (pinfunction "1_1") (pintype "passive"))
      (node (ref "U6") (pin "32") (pinfunction "SENSE2_32") (pintype "input"))
    )
    (net (code "188") (name "Net-(U6-VCP)") (class "Default")
      (node (ref "C32") (pin "2") (pinfunction "2_2") (pintype "passive"))
      (node (ref "U6") (pin "9") (pinfunction "VCP_9") (pintype "bidirectional"))
    )
    (net (code "189") (name "Net-(U6-VREG)") (class "Default")
      (node (ref "C36") (pin "2") (pinfunction "2_2") (pintype "passive"))
      (node (ref "U6") (pin "10") (pinfunction "VREG_10") (pintype "input"))
    )
    (net (code "190") (name "Net-(U7-CP1)") (class "Default")
      (node (ref "C38") (pin "1") (pinfunction "1_1") (pintype "passive"))
      (node (ref "U7") (pin "7") (pinfunction "CP1_7") (pintype "bidirectional"))
    )
    (net (code "191") (name "Net-(U7-CP2)") (class "Default")
      (node (ref "C38") (pin "2") (pinfunction "2_2") (pintype "passive"))
      (node (ref "U7") (pin "8") (pinfunction "CP2_8") (pintype "bidirectional"))
    )
    (net (code "192") (name "Net-(U7-OUT1A)") (class "Default")
      (node (ref "U7") (pin "27") (pinfunction "OUT1A_27") (pintype "output"))
      (node (ref "X14") (pin "3") (pinfunction "1_3") (pintype "passive"))
      (node (ref "X15") (pin "3") (pinfunction "1_3") (pintype "passive"))
    )
    (net (code "193") (name "Net-(U7-OUT1B)") (class "Default")
      (node (ref "U7") (pin "24") (pinfunction "OUT1B_24") (pintype "output"))
      (node (ref "X14") (pin "4") (pinfunction "1_4") (pintype "passive"))
      (node (ref "X15") (pin "4") (pinfunction "1_4") (pintype "passive"))
    )
    (net (code "194") (name "Net-(U7-OUT2A)") (class "Default")
      (node (ref "U7") (pin "30") (pinfunction "OUT2A_30") (pintype "output"))
      (node (ref "X14") (pin "2") (pinfunction "1_2") (pintype "passive"))
      (node (ref "X15") (pin "2") (pinfunction "1_2") (pintype "passive"))
    )
    (net (code "195") (name "Net-(U7-OUT2B)") (class "Default")
      (node (ref "U7") (pin "1") (pinfunction "OUT2B_1") (pintype "output"))
      (node (ref "X14") (pin "1") (pinfunction "1_1") (pintype "passive"))
      (node (ref "X15") (pin "1") (pinfunction "1_1") (pintype "passive"))
    )
    (net (code "196") (name "Net-(U7-RESET)") (class "Default")
      (node (ref "C18") (pin "1") (pinfunction "1_1") (pintype "passive"))
      (node (ref "R66") (pin "1") (pinfunction "1_1") (pintype "passive"))
      (node (ref "U7") (pin "13") (pinfunction "RESET_13") (pintype "input"))
      (node (ref "U7") (pin "15") (pinfunction "SLEEP_15") (pintype "input"))
      (node (ref "U7") (pin "16") (pinfunction "VDD_16") (pintype "power_in"))
    )
    (net (code "197") (name "Net-(U7-ROSC)") (class "Default")
      (node (ref "R17") (pin "2") (pinfunction "2_2") (pintype "passive"))
      (node (ref "U7") (pin "14") (pinfunction "ROSC_14") (pintype "input"))
    )
    (net (code "198") (name "Net-(U7-SENSE1)") (class "Default")
      (node (ref "R15") (pin "1") (pinfunction "1_1") (pintype "passive"))
      (node (ref "U7") (pin "25") (pinfunction "SENSE1_25") (pintype "input"))
    )
    (net (code "199") (name "Net-(U7-SENSE2)") (class "Default")
      (node (ref "R14") (pin "1") (pinfunction "1_1") (pintype "passive"))
      (node (ref "U7") (pin "32") (pinfunction "SENSE2_32") (pintype "input"))
    )
    (net (code "200") (name "Net-(U7-VCP)") (class "Default")
      (node (ref "C37") (pin "2") (pinfunction "2_2") (pintype "passive"))
      (node (ref "U7") (pin "9") (pinfunction "VCP_9") (pintype "bidirectional"))
    )
    (net (code "201") (name "Net-(U7-VREG)") (class "Default")
      (node (ref "C41") (pin "2") (pinfunction "2_2") (pintype "passive"))
      (node (ref "U7") (pin "10") (pinfunction "VREG_10") (pintype "input"))
    )
    (net (code "202") (name "Net-(U8-CP1)") (class "Default")
      (node (ref "C43") (pin "1") (pinfunction "1_1") (pintype "passive"))
      (node (ref "U8") (pin "7") (pinfunction "CP1_7") (pintype "bidirectional"))
    )
    (net (code "203") (name "Net-(U8-CP2)") (class "Default")
      (node (ref "C43") (pin "2") (pinfunction "2_2") (pintype "passive"))
      (node (ref "U8") (pin "8") (pinfunction "CP2_8") (pintype "bidirectional"))
    )
    (net (code "204") (name "Net-(U8-OUT1A)") (class "Default")
      (node (ref "U8") (pin "27") (pinfunction "OUT1A_27") (pintype "output"))
      (node (ref "X6") (pin "3") (pinfunction "1_3") (pintype "passive"))
    )
    (net (code "205") (name "Net-(U8-OUT1B)") (class "Default")
      (node (ref "U8") (pin "24") (pinfunction "OUT1B_24") (pintype "output"))
      (node (ref "X6") (pin "4") (pinfunction "1_4") (pintype "passive"))
    )
    (net (code "206") (name "Net-(U8-OUT2A)") (class "Default")
      (node (ref "U8") (pin "30") (pinfunction "OUT2A_30") (pintype "output"))
      (node (ref "X6") (pin "2") (pinfunction "1_2") (pintype "passive"))
    )
    (net (code "207") (name "Net-(U8-OUT2B)") (class "Default")
      (node (ref "U8") (pin "1") (pinfunction "OUT2B_1") (pintype "output"))
      (node (ref "X6") (pin "1") (pinfunction "1_1") (pintype "passive"))
    )
    (net (code "208") (name "Net-(U8-RESET)") (class "Default")
      (node (ref "C17") (pin "1") (pinfunction "1_1") (pintype "passive"))
      (node (ref "R67") (pin "1") (pinfunction "1_1") (pintype "passive"))
      (node (ref "U8") (pin "13") (pinfunction "RESET_13") (pintype "input"))
      (node (ref "U8") (pin "15") (pinfunction "SLEEP_15") (pintype "input"))
      (node (ref "U8") (pin "16") (pinfunction "VDD_16") (pintype "power_in"))
    )
    (net (code "209") (name "Net-(U8-ROSC)") (class "Default")
      (node (ref "R22") (pin "2") (pinfunction "2_2") (pintype "passive"))
      (node (ref "U8") (pin "14") (pinfunction "ROSC_14") (pintype "input"))
    )
    (net (code "210") (name "Net-(U8-SENSE1)") (class "Default")
      (node (ref "R20") (pin "1") (pinfunction "1_1") (pintype "passive"))
      (node (ref "U8") (pin "25") (pinfunction "SENSE1_25") (pintype "input"))
    )
    (net (code "211") (name "Net-(U8-SENSE2)") (class "Default")
      (node (ref "R19") (pin "1") (pinfunction "1_1") (pintype "passive"))
      (node (ref "U8") (pin "32") (pinfunction "SENSE2_32") (pintype "input"))
    )
    (net (code "212") (name "Net-(U8-VCP)") (class "Default")
      (node (ref "C42") (pin "2") (pinfunction "2_2") (pintype "passive"))
      (node (ref "U8") (pin "9") (pinfunction "VCP_9") (pintype "bidirectional"))
    )
    (net (code "213") (name "Net-(U8-VREG)") (class "Default")
      (node (ref "C46") (pin "2") (pinfunction "2_2") (pintype "passive"))
      (node (ref "U8") (pin "10") (pinfunction "VREG_10") (pintype "input"))
    )
    (net (code "214") (name "Net-(U9-CP1)") (class "Default")
      (node (ref "C48") (pin "1") (pinfunction "1_1") (pintype "passive"))
      (node (ref "U9") (pin "7") (pinfunction "CP1_7") (pintype "bidirectional"))
    )
    (net (code "215") (name "Net-(U9-CP2)") (class "Default")
      (node (ref "C48") (pin "2") (pinfunction "2_2") (pintype "passive"))
      (node (ref "U9") (pin "8") (pinfunction "CP2_8") (pintype "bidirectional"))
    )
    (net (code "216") (name "Net-(U9-OUT1A)") (class "Default")
      (node (ref "U9") (pin "27") (pinfunction "OUT1A_27") (pintype "output"))
      (node (ref "X7") (pin "3") (pinfunction "1_3") (pintype "passive"))
    )
    (net (code "217") (name "Net-(U9-OUT1B)") (class "Default")
      (node (ref "U9") (pin "24") (pinfunction "OUT1B_24") (pintype "output"))
      (node (ref "X7") (pin "4") (pinfunction "1_4") (pintype "passive"))
    )
    (net (code "218") (name "Net-(U9-OUT2A)") (class "Default")
      (node (ref "U9") (pin "30") (pinfunction "OUT2A_30") (pintype "output"))
      (node (ref "X7") (pin "2") (pinfunction "1_2") (pintype "passive"))
    )
    (net (code "219") (name "Net-(U9-OUT2B)") (class "Default")
      (node (ref "U9") (pin "1") (pinfunction "OUT2B_1") (pintype "output"))
      (node (ref "X7") (pin "1") (pinfunction "1_1") (pintype "passive"))
    )
    (net (code "220") (name "Net-(U9-RESET)") (class "Default")
      (node (ref "C4") (pin "1") (pinfunction "1_1") (pintype "passive"))
      (node (ref "R68") (pin "1") (pinfunction "1_1") (pintype "passive"))
      (node (ref "U9") (pin "13") (pinfunction "RESET_13") (pintype "input"))
      (node (ref "U9") (pin "15") (pinfunction "SLEEP_15") (pintype "input"))
      (node (ref "U9") (pin "16") (pinfunction "VDD_16") (pintype "power_in"))
    )
    (net (code "221") (name "Net-(U9-ROSC)") (class "Default")
      (node (ref "R26") (pin "2") (pinfunction "2_2") (pintype "passive"))
      (node (ref "U9") (pin "14") (pinfunction "ROSC_14") (pintype "input"))
    )
    (net (code "222") (name "Net-(U9-SENSE1)") (class "Default")
      (node (ref "R24") (pin "1") (pinfunction "1_1") (pintype "passive"))
      (node (ref "U9") (pin "25") (pinfunction "SENSE1_25") (pintype "input"))
    )
    (net (code "223") (name "Net-(U9-SENSE2)") (class "Default")
      (node (ref "R23") (pin "1") (pinfunction "1_1") (pintype "passive"))
      (node (ref "U9") (pin "32") (pinfunction "SENSE2_32") (pintype "input"))
    )
    (net (code "224") (name "Net-(U9-VCP)") (class "Default")
      (node (ref "C47") (pin "2") (pinfunction "2_2") (pintype "passive"))
      (node (ref "U9") (pin "9") (pinfunction "VCP_9") (pintype "bidirectional"))
    )
    (net (code "225") (name "Net-(U9-VREG)") (class "Default")
      (node (ref "C51") (pin "2") (pinfunction "2_2") (pintype "passive"))
      (node (ref "U9") (pin "10") (pinfunction "VREG_10") (pintype "input"))
    )
    (net (code "226") (name "Net-(U10-VOC)") (class "Default")
      (node (ref "R34") (pin "1") (pinfunction "1_1") (pintype "passive"))
      (node (ref "U10") (pin "12") (pinfunction "VOC_12") (pintype "bidirectional"))
    )
    (net (code "227") (name "Net-(X3B-S)") (class "Default")
      (node (ref "R27") (pin "1") (pinfunction "1_1") (pintype "passive"))
      (node (ref "R39") (pin "2") (pinfunction "2_2") (pintype "passive"))
      (node (ref "X3") (pin "2") (pinfunction "S_2") (pintype "passive"))
    )
    (net (code "228") (name "Net-(X27B-S)") (class "Default")
      (node (ref "R31") (pin "1") (pinfunction "1_1") (pintype "passive"))
      (node (ref "R32") (pin "2") (pinfunction "2_2") (pintype "passive"))
      (node (ref "X27") (pin "2") (pinfunction "S_2") (pintype "passive"))
    )
    (net (code "229") (name "Net-(X28B-S)") (class "Default")
      (node (ref "R36") (pin "1") (pinfunction "1_1") (pintype "passive"))
      (node (ref "R37") (pin "2") (pinfunction "2_2") (pintype "passive"))
      (node (ref "X28") (pin "2") (pinfunction "S_2") (pintype "passive"))
    )
    (net (code "230") (name "Net-(X29B-S)") (class "Default")
      (node (ref "R28") (pin "2") (pinfunction "2_2") (pintype "passive"))
      (node (ref "R38") (pin "1") (pinfunction "1_1") (pintype "passive"))
      (node (ref "X29") (pin "2") (pinfunction "S_2") (pintype "passive"))
    )
    (net (code "231") (name "Net-(X33C-1)") (class "Default")
      (node (ref "F3") (pin "P$1") (pinfunction "P$1_P$1") (pintype "bidirectional"))
      (node (ref "X33") (pin "3") (pinfunction "1_3") (pintype "passive"))
    )
    (net (code "232") (name "VCC") (class "Default")
      (node (ref "C25") (pin "1") (pinfunction "1_1") (pintype "passive"))
      (node (ref "C30") (pin "1") (pinfunction "1_1") (pintype "passive"))
      (node (ref "C52") (pin "1") (pinfunction "1_1") (pintype "passive"))
      (node (ref "C53") (pin "1") (pinfunction "1_1") (pintype "passive"))
      (node (ref "C55") (pin "1") (pinfunction "1_1") (pintype "passive"))
      (node (ref "C68") (pin "2") (pinfunction "2_2") (pintype "passive"))
      (node (ref "C69") (pin "1") (pinfunction "1_1") (pintype "passive"))
      (node (ref "C7") (pin "1") (pinfunction "1_1") (pintype "passive"))
      (node (ref "C8") (pin "1") (pinfunction "1_1") (pintype "passive"))
      (node (ref "C9") (pin "1") (pinfunction "1_1") (pintype "passive"))
      (node (ref "D5") (pin "C") (pinfunction "C_C") (pintype "passive"))
      (node (ref "L2") (pin "1") (pinfunction "1_1") (pintype "passive"))
      (node (ref "L3") (pin "P$2") (pinfunction "2_P$2") (pintype "passive"))
      (node (ref "R13") (pin "2") (pinfunction "2_2") (pintype "passive"))
      (node (ref "R27") (pin "2") (pinfunction "2_2") (pintype "passive"))
      (node (ref "R29") (pin "2") (pinfunction "2_2") (pintype "passive"))
      (node (ref "R30") (pin "1") (pinfunction "1_1") (pintype "passive"))
      (node (ref "R31") (pin "2") (pinfunction "2_2") (pintype "passive"))
      (node (ref "R35") (pin "1") (pinfunction "1_1") (pintype "passive"))
      (node (ref "R36") (pin "2") (pinfunction "2_2") (pintype "passive"))
      (node (ref "R38") (pin "2") (pinfunction "2_2") (pintype "passive"))
      (node (ref "R44") (pin "2") (pinfunction "2_2") (pintype "passive"))
      (node (ref "R45") (pin "2") (pinfunction "2_2") (pintype "passive"))
      (node (ref "R46") (pin "2") (pinfunction "2_2") (pintype "passive"))
      (node (ref "R59") (pin "1") (pinfunction "1_1") (pintype "passive"))
      (node (ref "R60") (pin "1") (pinfunction "1_1") (pintype "passive"))
      (node (ref "R61") (pin "1") (pinfunction "1_1") (pintype "passive"))
      (node (ref "R62") (pin "1") (pinfunction "1_1") (pintype "passive"))
      (node (ref "R63") (pin "1") (pinfunction "1_1") (pintype "passive"))
      (node (ref "R65") (pin "2") (pinfunction "2_2") (pintype "passive"))
      (node (ref "R66") (pin "2") (pinfunction "2_2") (pintype "passive"))
      (node (ref "R67") (pin "2") (pinfunction "2_2") (pintype "passive"))
      (node (ref "R68") (pin "2") (pinfunction "2_2") (pintype "passive"))
      (node (ref "U10") (pin "10") (pinfunction "VDD2B_10") (pintype "bidirectional"))
      (node (ref "U10") (pin "16") (pinfunction "VDD2A_16") (pintype "bidirectional"))
      (node (ref "U2") (pin "10") (pinfunction "VCC_10") (pintype "power_in"))
      (node (ref "U2") (pin "31") (pinfunction "VCC1_31") (pintype "power_in"))
      (node (ref "U2") (pin "61") (pinfunction "VCC2_61") (pintype "power_in"))
      (node (ref "U2") (pin "80") (pinfunction "VCC3_80") (pintype "power_in"))
      (node (ref "U4") (pin "P06") (pinfunction "VDD_P06") (pintype "bidirectional"))
      (node (ref "X1") (pin "2") (pinfunction "S_2") (pintype "passive"))
      (node (ref "X10") (pin "1") (pinfunction "S_1") (pintype "passive"))
      (node (ref "X12") (pin "1") (pinfunction "1_1") (pintype "passive"))
      (node (ref "X13") (pin "1") (pinfunction "1_1") (pintype "passive"))
      (node (ref "X13") (pin "2") (pinfunction "2_2") (pintype "passive"))
      (node (ref "X18") (pin "2") (pinfunction "2_2") (pintype "passive"))
      (node (ref "X20") (pin "1") (pinfunction "1_1") (pintype "passive"))
      (node (ref "X21") (pin "3") (pinfunction "S_3") (pintype "passive"))
      (node (ref "X22") (pin "3") (pinfunction "S_3") (pintype "passive"))
      (node (ref "X23") (pin "3") (pinfunction "S_3") (pintype "passive"))
      (node (ref "X24") (pin "3") (pinfunction "S_3") (pintype "passive"))
      (node (ref "X25") (pin "3") (pinfunction "S_3") (pintype "passive"))
      (node (ref "X26") (pin "3") (pinfunction "S_3") (pintype "passive"))
      (node (ref "X31") (pin "1") (pinfunction "1_1") (pintype "passive"))
      (node (ref "X32") (pin "1") (pinfunction "1_1") (pintype "passive"))
      (node (ref "X34") (pin "1") (pinfunction "1_1") (pintype "passive"))
      (node (ref "X39") (pin "1") (pinfunction "1_1") (pintype "passive"))
      (node (ref "X40") (pin "1") (pinfunction "1_1") (pintype "passive"))
      (node (ref "X5") (pin "2") (pinfunction "S_2") (pintype "passive"))
    )
    (net (code "233") (name "unconnected-(D9-PadC)") (class "Default")
      (node (ref "D9") (pin "C") (pinfunction "C_C") (pintype "passive"))
    )
    (net (code "234") (name "unconnected-(D21-PadA)") (class "Default")
      (node (ref "D21") (pin "A") (pinfunction "A_A") (pintype "passive"))
    )
    (net (code "235") (name "unconnected-(D21-PadC)") (class "Default")
      (node (ref "D21") (pin "C") (pinfunction "C_C") (pintype "passive"))
    )
    (net (code "236") (name "unconnected-(D22-PadA)") (class "Default")
      (node (ref "D22") (pin "A") (pinfunction "A_A") (pintype "passive"))
    )
    (net (code "237") (name "unconnected-(D22-PadC)") (class "Default")
      (node (ref "D22") (pin "C") (pinfunction "C_C") (pintype "passive"))
    )
    (net (code "238") (name "unconnected-(D23-PadA)") (class "Default")
      (node (ref "D23") (pin "A") (pinfunction "A_A") (pintype "passive"))
    )
    (net (code "239") (name "unconnected-(D23-PadC)") (class "Default")
      (node (ref "D23") (pin "C") (pinfunction "C_C") (pintype "passive"))
    )
    (net (code "240") (name "unconnected-(D24-PadA)") (class "Default")
      (node (ref "D24") (pin "A") (pinfunction "A_A") (pintype "passive"))
    )
    (net (code "241") (name "unconnected-(D24-PadC)") (class "Default")
      (node (ref "D24") (pin "C") (pinfunction "C_C") (pintype "passive"))
    )
    (net (code "242") (name "unconnected-(D25-PadA)") (class "Default")
      (node (ref "D25") (pin "A") (pinfunction "A_A") (pintype "passive"))
    )
    (net (code "243") (name "unconnected-(D25-PadC)") (class "Default")
      (node (ref "D25") (pin "C") (pinfunction "C_C") (pintype "passive"))
    )
    (net (code "244") (name "unconnected-(D26-PadA)") (class "Default")
      (node (ref "D26") (pin "A") (pinfunction "A_A") (pintype "passive"))
    )
    (net (code "245") (name "unconnected-(D26-PadC)") (class "Default")
      (node (ref "D26") (pin "C") (pinfunction "C_C") (pintype "passive"))
    )
    (net (code "246") (name "unconnected-(D27-PadA)") (class "Default")
      (node (ref "D27") (pin "A") (pinfunction "A_A") (pintype "passive"))
    )
    (net (code "247") (name "unconnected-(D27-PadC)") (class "Default")
      (node (ref "D27") (pin "C") (pinfunction "C_C") (pintype "passive"))
    )
    (net (code "248") (name "unconnected-(D28-PadA)") (class "Default")
      (node (ref "D28") (pin "A") (pinfunction "A_A") (pintype "passive"))
    )
    (net (code "249") (name "unconnected-(D28-PadC)") (class "Default")
      (node (ref "D28") (pin "C") (pinfunction "C_C") (pintype "passive"))
    )
    (net (code "250") (name "unconnected-(D29-PadA)") (class "Default")
      (node (ref "D29") (pin "A") (pinfunction "A_A") (pintype "passive"))
    )
    (net (code "251") (name "unconnected-(D29-PadC)") (class "Default")
      (node (ref "D29") (pin "C") (pinfunction "C_C") (pintype "passive"))
    )
    (net (code "252") (name "unconnected-(D30-PadA)") (class "Default")
      (node (ref "D30") (pin "A") (pinfunction "A_A") (pintype "passive"))
    )
    (net (code "253") (name "unconnected-(D30-PadC)") (class "Default")
      (node (ref "D30") (pin "C") (pinfunction "C_C") (pintype "passive"))
    )
    (net (code "254") (name "unconnected-(D31-PadA)") (class "Default")
      (node (ref "D31") (pin "A") (pinfunction "A_A") (pintype "passive"))
    )
    (net (code "255") (name "unconnected-(D31-PadC)") (class "Default")
      (node (ref "D31") (pin "C") (pinfunction "C_C") (pintype "passive"))
    )
    (net (code "256") (name "unconnected-(D32-PadA)") (class "Default")
      (node (ref "D32") (pin "A") (pinfunction "A_A") (pintype "passive"))
    )
    (net (code "257") (name "unconnected-(D32-PadC)") (class "Default")
      (node (ref "D32") (pin "C") (pinfunction "C_C") (pintype "passive"))
    )
    (net (code "258") (name "unconnected-(D33-PadA)") (class "Default")
      (node (ref "D33") (pin "A") (pinfunction "A_A") (pintype "passive"))
    )
    (net (code "259") (name "unconnected-(D33-PadC)") (class "Default")
      (node (ref "D33") (pin "C") (pinfunction "C_C") (pintype "passive"))
    )
    (net (code "260") (name "unconnected-(D34-PadA)") (class "Default")
      (node (ref "D34") (pin "A") (pinfunction "A_A") (pintype "passive"))
    )
    (net (code "261") (name "unconnected-(D34-PadC)") (class "Default")
      (node (ref "D34") (pin "C") (pinfunction "C_C") (pintype "passive"))
    )
    (net (code "262") (name "unconnected-(D35-PadA)") (class "Default")
      (node (ref "D35") (pin "A") (pinfunction "A_A") (pintype "passive"))
    )
    (net (code "263") (name "unconnected-(D35-PadC)") (class "Default")
      (node (ref "D35") (pin "C") (pinfunction "C_C") (pintype "passive"))
    )
    (net (code "264") (name "unconnected-(D36-PadA)") (class "Default")
      (node (ref "D36") (pin "A") (pinfunction "A_A") (pintype "passive"))
    )
    (net (code "265") (name "unconnected-(D36-PadC)") (class "Default")
      (node (ref "D36") (pin "C") (pinfunction "C_C") (pintype "passive"))
    )
    (net (code "266") (name "unconnected-(D37-PadA)") (class "Default")
      (node (ref "D37") (pin "A") (pinfunction "A_A") (pintype "passive"))
    )
    (net (code "267") (name "unconnected-(D37-PadC)") (class "Default")
      (node (ref "D37") (pin "C") (pinfunction "C_C") (pintype "passive"))
    )
    (net (code "268") (name "unconnected-(D38-PadA)") (class "Default")
      (node (ref "D38") (pin "A") (pinfunction "A_A") (pintype "passive"))
    )
    (net (code "269") (name "unconnected-(D38-PadC)") (class "Default")
      (node (ref "D38") (pin "C") (pinfunction "C_C") (pintype "passive"))
    )
    (net (code "270") (name "unconnected-(D39-PadA)") (class "Default")
      (node (ref "D39") (pin "A") (pinfunction "A_A") (pintype "passive"))
    )
    (net (code "271") (name "unconnected-(D39-PadC)") (class "Default")
      (node (ref "D39") (pin "C") (pinfunction "C_C") (pintype "passive"))
    )
    (net (code "272") (name "unconnected-(RN5-Pad1)") (class "Default")
      (node (ref "RN5") (pin "1") (pinfunction "1_1") (pintype "passive"))
    )
    (net (code "273") (name "unconnected-(RN5A-2-Pad8)") (class "Default")
      (node (ref "RN5") (pin "8") (pinfunction "2_8") (pintype "passive"))
    )
    (net (code "274") (name "unconnected-(U3-NC-Pad2)") (class "Default")
      (node (ref "U3") (pin "2") (pinfunction "NC_2") (pintype "bidirectional"))
    )
    (net (code "275") (name "unconnected-(U3-NC1-Pad3)") (class "Default")
      (node (ref "U3") (pin "3") (pinfunction "NC1_3") (pintype "bidirectional"))
    )
    (net (code "276") (name "unconnected-(U5-NC1-Pad2)") (class "Default")
      (node (ref "U5") (pin "2") (pinfunction "NC1_2") (pintype "output"))
    )
    (net (code "277") (name "unconnected-(U5-NC2-Pad4)") (class "Default")
      (node (ref "U5") (pin "4") (pinfunction "NC2_4") (pintype "output"))
    )
    (net (code "278") (name "unconnected-(U5-NC3-Pad21)") (class "Default")
      (node (ref "U5") (pin "21") (pinfunction "NC3_21") (pintype "output"))
    )
    (net (code "279") (name "unconnected-(U5-NC4-Pad23)") (class "Default")
      (node (ref "U5") (pin "23") (pinfunction "NC4_23") (pintype "output"))
    )
    (net (code "280") (name "unconnected-(U5-NC5-Pad26)") (class "Default")
      (node (ref "U5") (pin "26") (pinfunction "NC5_26") (pintype "output"))
    )
    (net (code "281") (name "unconnected-(U5-NC6-Pad28)") (class "Default")
      (node (ref "U5") (pin "28") (pinfunction "NC6_28") (pintype "output"))
    )
    (net (code "282") (name "unconnected-(U5-NC7-Pad29)") (class "Default")
      (node (ref "U5") (pin "29") (pinfunction "NC7_29") (pintype "output"))
    )
    (net (code "283") (name "unconnected-(U5-NC8-Pad31)") (class "Default")
      (node (ref "U5") (pin "31") (pinfunction "NC8_31") (pintype "output"))
    )
    (net (code "284") (name "unconnected-(U6-NC1-Pad2)") (class "Default")
      (node (ref "U6") (pin "2") (pinfunction "NC1_2") (pintype "output"))
    )
    (net (code "285") (name "unconnected-(U6-NC2-Pad4)") (class "Default")
      (node (ref "U6") (pin "4") (pinfunction "NC2_4") (pintype "output"))
    )
    (net (code "286") (name "unconnected-(U6-NC3-Pad21)") (class "Default")
      (node (ref "U6") (pin "21") (pinfunction "NC3_21") (pintype "output"))
    )
    (net (code "287") (name "unconnected-(U6-NC4-Pad23)") (class "Default")
      (node (ref "U6") (pin "23") (pinfunction "NC4_23") (pintype "output"))
    )
    (net (code "288") (name "unconnected-(U6-NC5-Pad26)") (class "Default")
      (node (ref "U6") (pin "26") (pinfunction "NC5_26") (pintype "output"))
    )
    (net (code "289") (name "unconnected-(U6-NC6-Pad28)") (class "Default")
      (node (ref "U6") (pin "28") (pinfunction "NC6_28") (pintype "output"))
    )
    (net (code "290") (name "unconnected-(U6-NC7-Pad29)") (class "Default")
      (node (ref "U6") (pin "29") (pinfunction "NC7_29") (pintype "output"))
    )
    (net (code "291") (name "unconnected-(U6-NC8-Pad31)") (class "Default")
      (node (ref "U6") (pin "31") (pinfunction "NC8_31") (pintype "output"))
    )
    (net (code "292") (name "unconnected-(U7-NC1-Pad2)") (class "Default")
      (node (ref "U7") (pin "2") (pinfunction "NC1_2") (pintype "output"))
    )
    (net (code "293") (name "unconnected-(U7-NC2-Pad4)") (class "Default")
      (node (ref "U7") (pin "4") (pinfunction "NC2_4") (pintype "output"))
    )
    (net (code "294") (name "unconnected-(U7-NC3-Pad21)") (class "Default")
      (node (ref "U7") (pin "21") (pinfunction "NC3_21") (pintype "output"))
    )
    (net (code "295") (name "unconnected-(U7-NC4-Pad23)") (class "Default")
      (node (ref "U7") (pin "23") (pinfunction "NC4_23") (pintype "output"))
    )
    (net (code "296") (name "unconnected-(U7-NC5-Pad26)") (class "Default")
      (node (ref "U7") (pin "26") (pinfunction "NC5_26") (pintype "output"))
    )
    (net (code "297") (name "unconnected-(U7-NC6-Pad28)") (class "Default")
      (node (ref "U7") (pin "28") (pinfunction "NC6_28") (pintype "output"))
    )
    (net (code "298") (name "unconnected-(U7-NC7-Pad29)") (class "Default")
      (node (ref "U7") (pin "29") (pinfunction "NC7_29") (pintype "output"))
    )
    (net (code "299") (name "unconnected-(U7-NC8-Pad31)") (class "Default")
      (node (ref "U7") (pin "31") (pinfunction "NC8_31") (pintype "output"))
    )
    (net (code "300") (name "unconnected-(U8-NC1-Pad2)") (class "Default")
      (node (ref "U8") (pin "2") (pinfunction "NC1_2") (pintype "output"))
    )
    (net (code "301") (name "unconnected-(U8-NC2-Pad4)") (class "Default")
      (node (ref "U8") (pin "4") (pinfunction "NC2_4") (pintype "output"))
    )
    (net (code "302") (name "unconnected-(U8-NC3-Pad21)") (class "Default")
      (node (ref "U8") (pin "21") (pinfunction "NC3_21") (pintype "output"))
    )
    (net (code "303") (name "unconnected-(U8-NC4-Pad23)") (class "Default")
      (node (ref "U8") (pin "23") (pinfunction "NC4_23") (pintype "output"))
    )
    (net (code "304") (name "unconnected-(U8-NC5-Pad26)") (class "Default")
      (node (ref "U8") (pin "26") (pinfunction "NC5_26") (pintype "output"))
    )
    (net (code "305") (name "unconnected-(U8-NC6-Pad28)") (class "Default")
      (node (ref "U8") (pin "28") (pinfunction "NC6_28") (pintype "output"))
    )
    (net (code "306") (name "unconnected-(U8-NC7-Pad29)") (class "Default")
      (node (ref "U8") (pin "29") (pinfunction "NC7_29") (pintype "output"))
    )
    (net (code "307") (name "unconnected-(U8-NC8-Pad31)") (class "Default")
      (node (ref "U8") (pin "31") (pinfunction "NC8_31") (pintype "output"))
    )
    (net (code "308") (name "unconnected-(U9-NC1-Pad2)") (class "Default")
      (node (ref "U9") (pin "2") (pinfunction "NC1_2") (pintype "output"))
    )
    (net (code "309") (name "unconnected-(U9-NC2-Pad4)") (class "Default")
      (node (ref "U9") (pin "4") (pinfunction "NC2_4") (pintype "output"))
    )
    (net (code "310") (name "unconnected-(U9-NC3-Pad21)") (class "Default")
      (node (ref "U9") (pin "21") (pinfunction "NC3_21") (pintype "output"))
    )
    (net (code "311") (name "unconnected-(U9-NC4-Pad23)") (class "Default")
      (node (ref "U9") (pin "23") (pinfunction "NC4_23") (pintype "output"))
    )
    (net (code "312") (name "unconnected-(U9-NC5-Pad26)") (class "Default")
      (node (ref "U9") (pin "26") (pinfunction "NC5_26") (pintype "output"))
    )
    (net (code "313") (name "unconnected-(U9-NC6-Pad28)") (class "Default")
      (node (ref "U9") (pin "28") (pinfunction "NC6_28") (pintype "output"))
    )
    (net (code "314") (name "unconnected-(U9-NC7-Pad29)") (class "Default")
      (node (ref "U9") (pin "29") (pinfunction "NC7_29") (pintype "output"))
    )
    (net (code "315") (name "unconnected-(U9-NC8-Pad31)") (class "Default")
      (node (ref "U9") (pin "31") (pinfunction "NC8_31") (pintype "output"))
    )
    (net (code "316") (name "unconnected-(U10-VOB-Pad13)") (class "Default")
      (node (ref "U10") (pin "13") (pinfunction "VOB_13") (pintype "bidirectional"))
    )
    (net (code "317") (name "unconnected-(X12-Pad8)") (class "Default")
      (node (ref "X12") (pin "8") (pinfunction "8_8") (pintype "passive"))
    )
  )
)
